# Fuel_Cell_Controller_V1.net
KiCad netlist of a schematic drawn in EAGLE
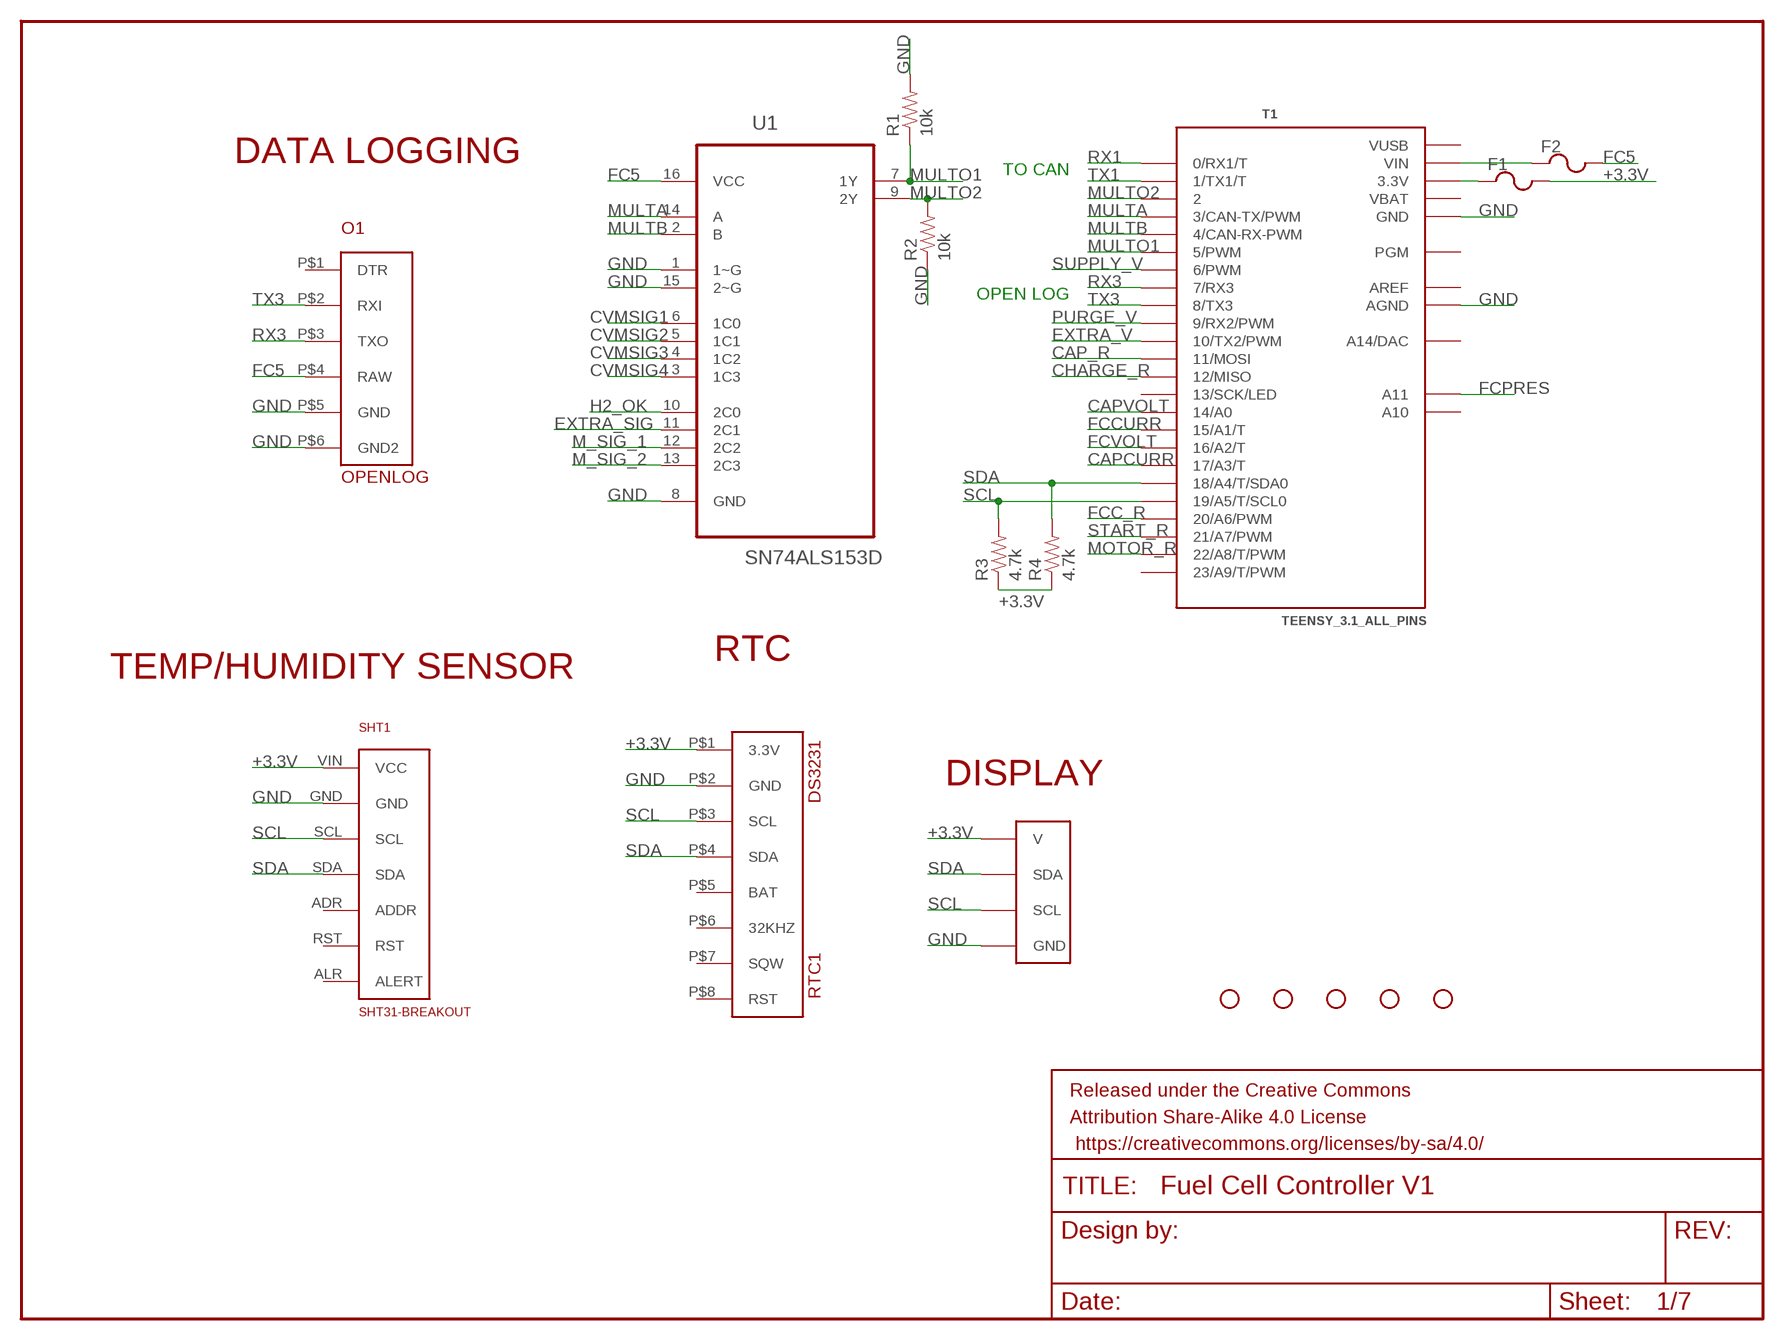
[diagram p0: schematic, sheet 1]
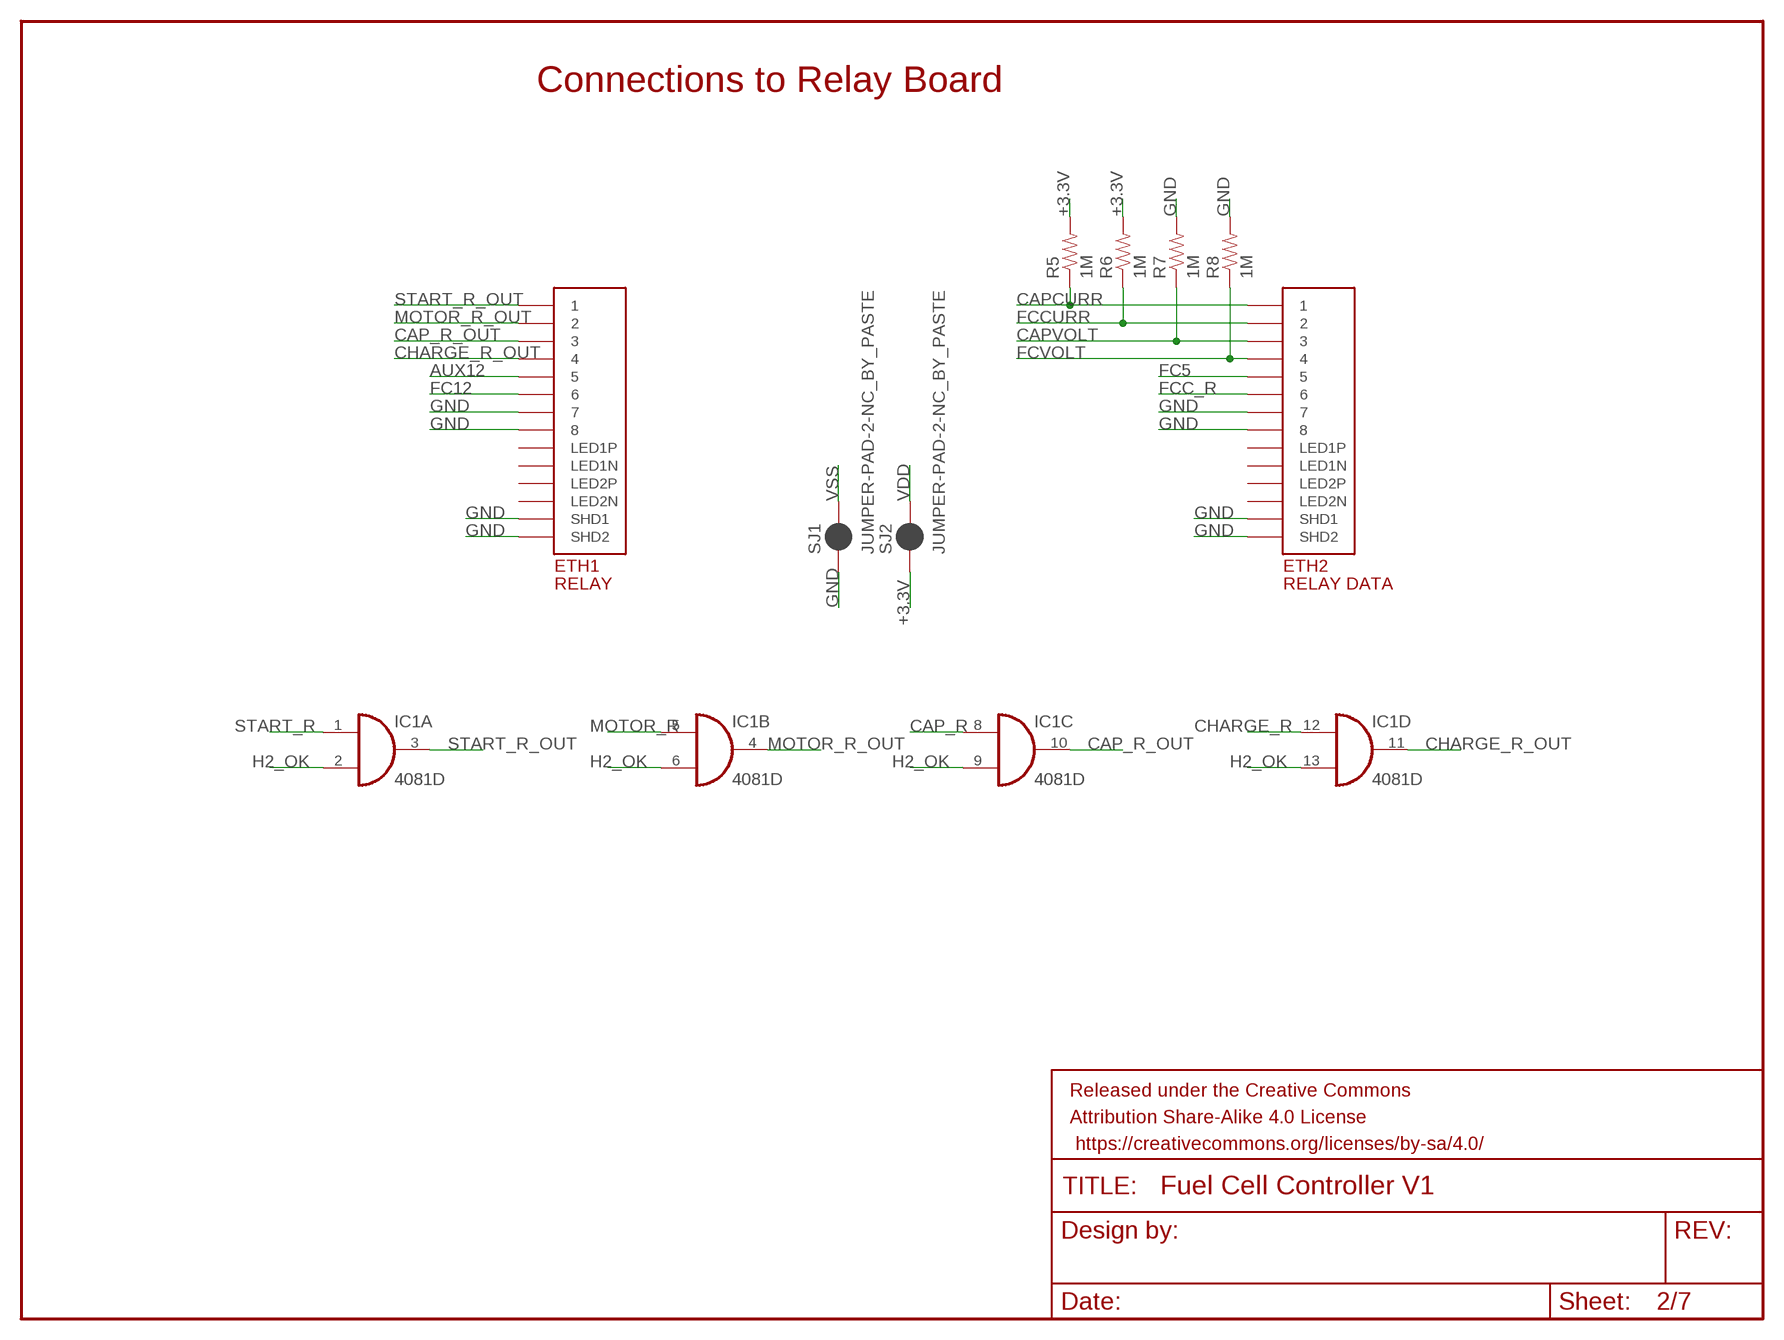
[diagram p1: schematic, sheet 2]
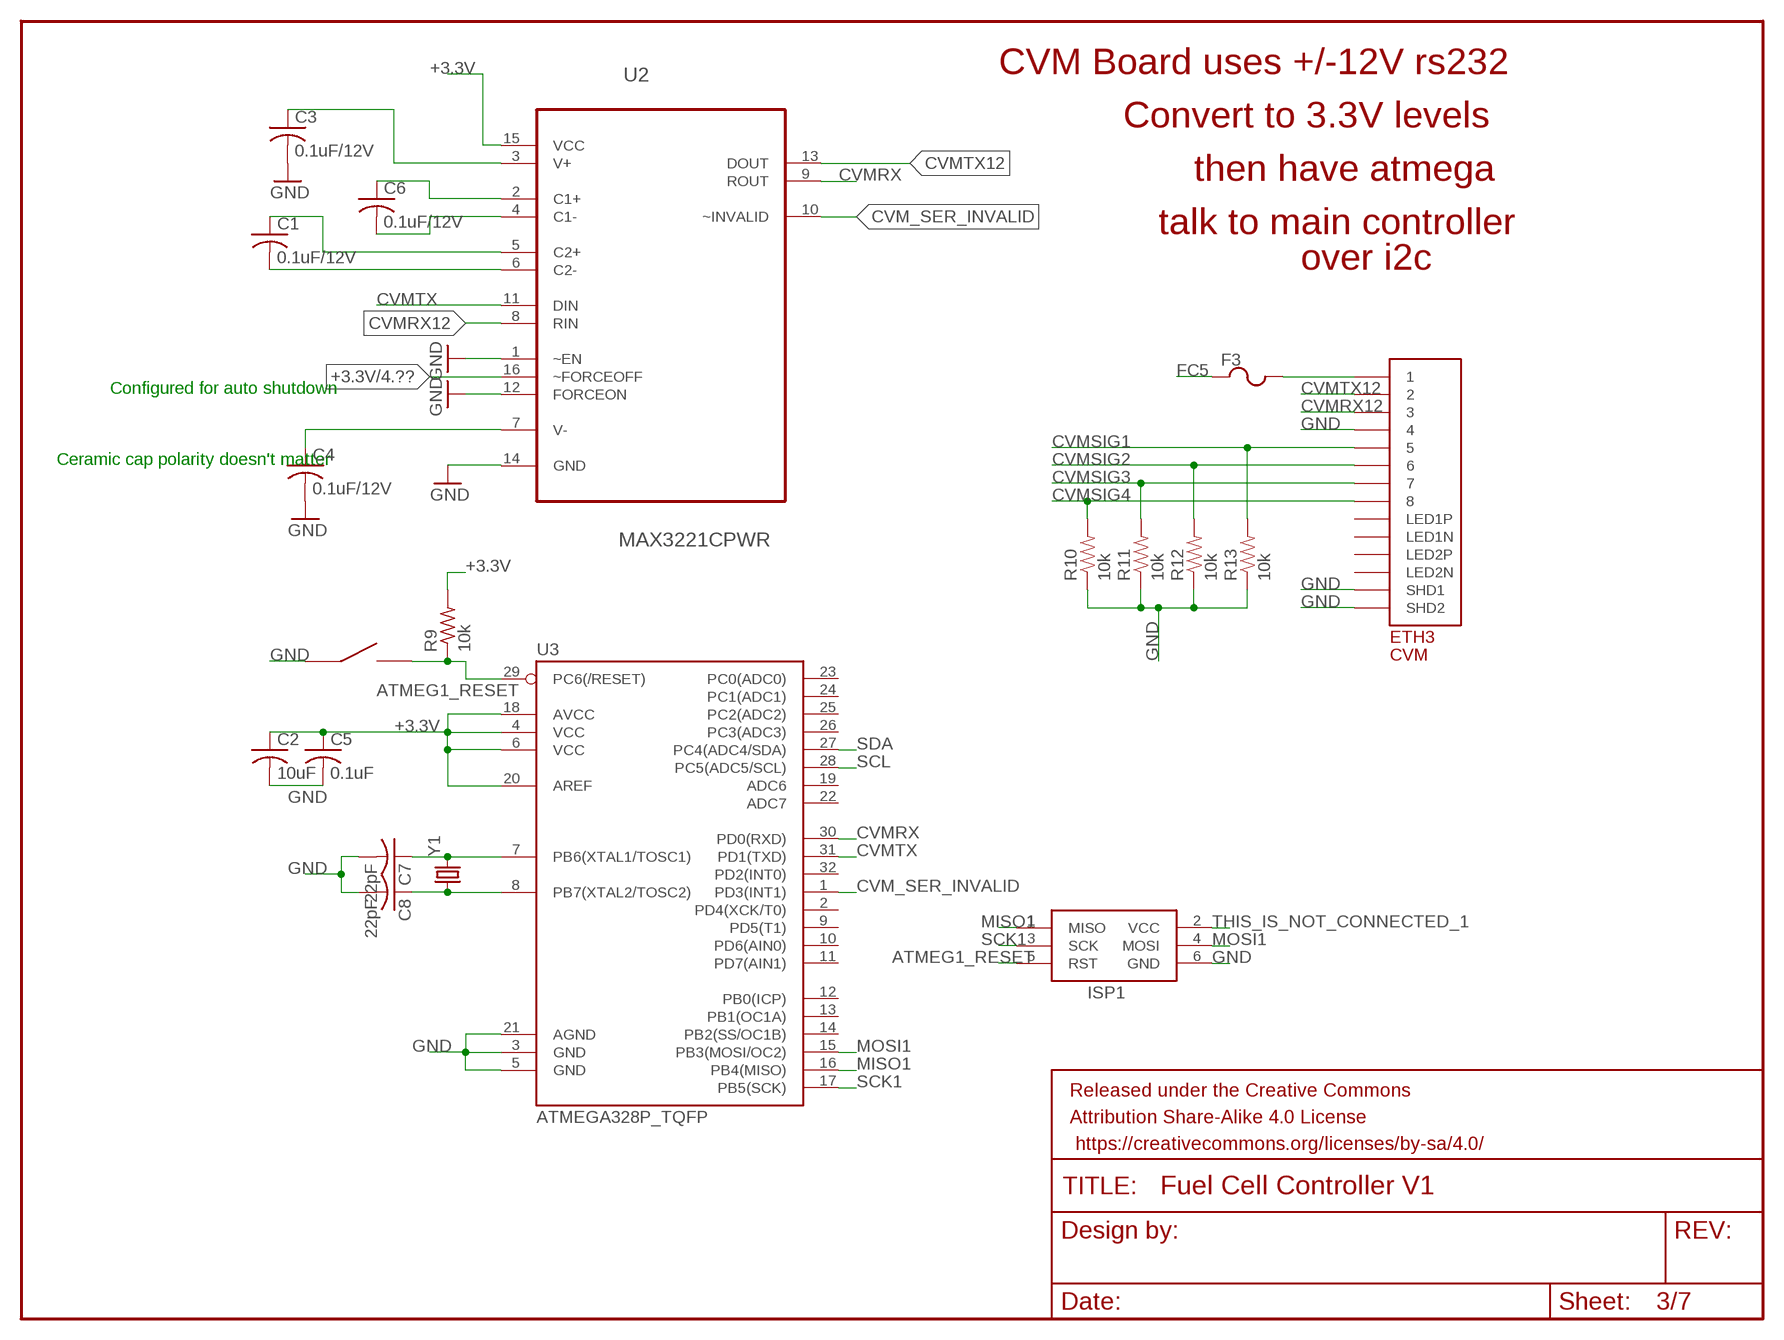
[diagram p2: schematic, sheet 3]
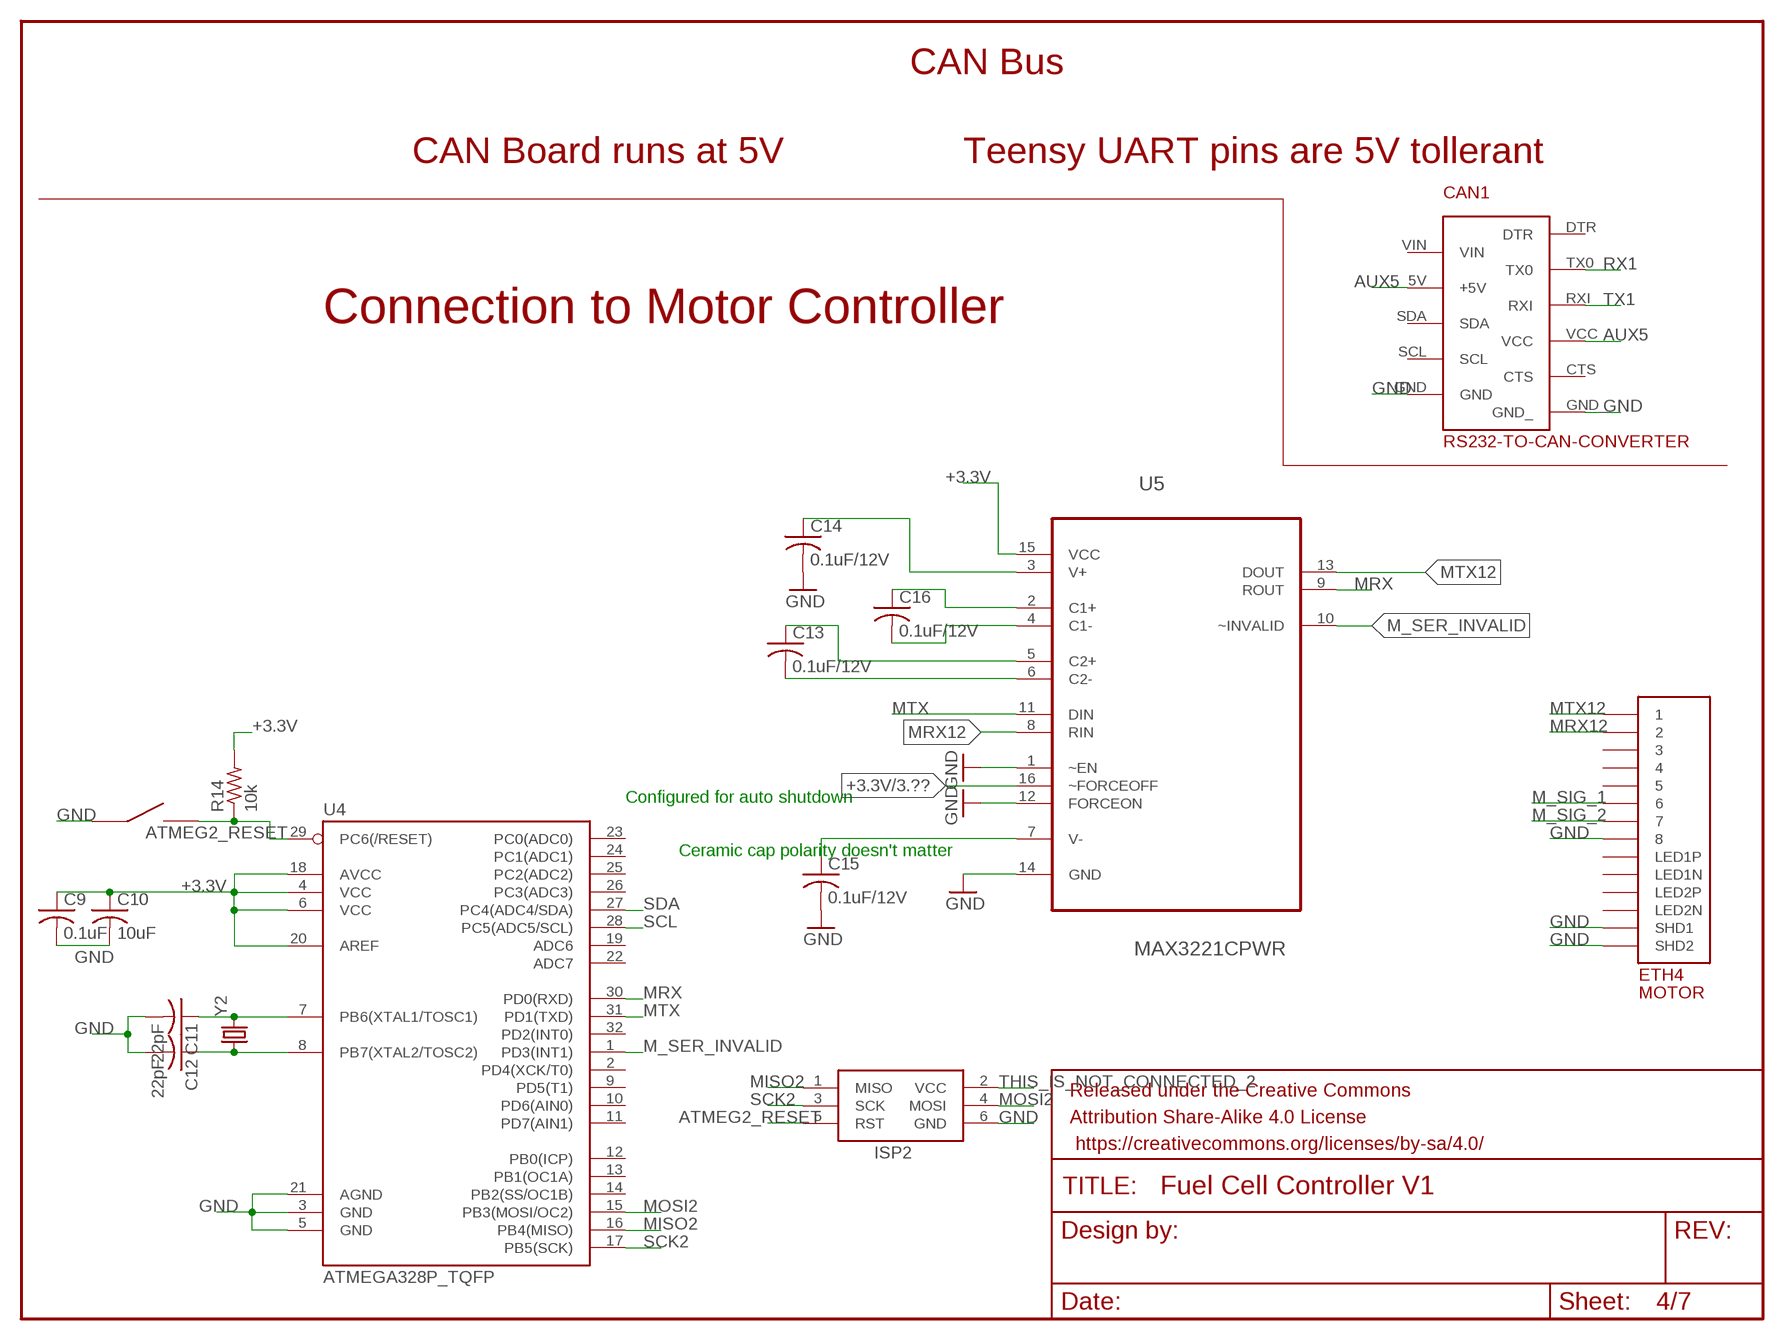
[diagram p3: schematic, sheet 4]
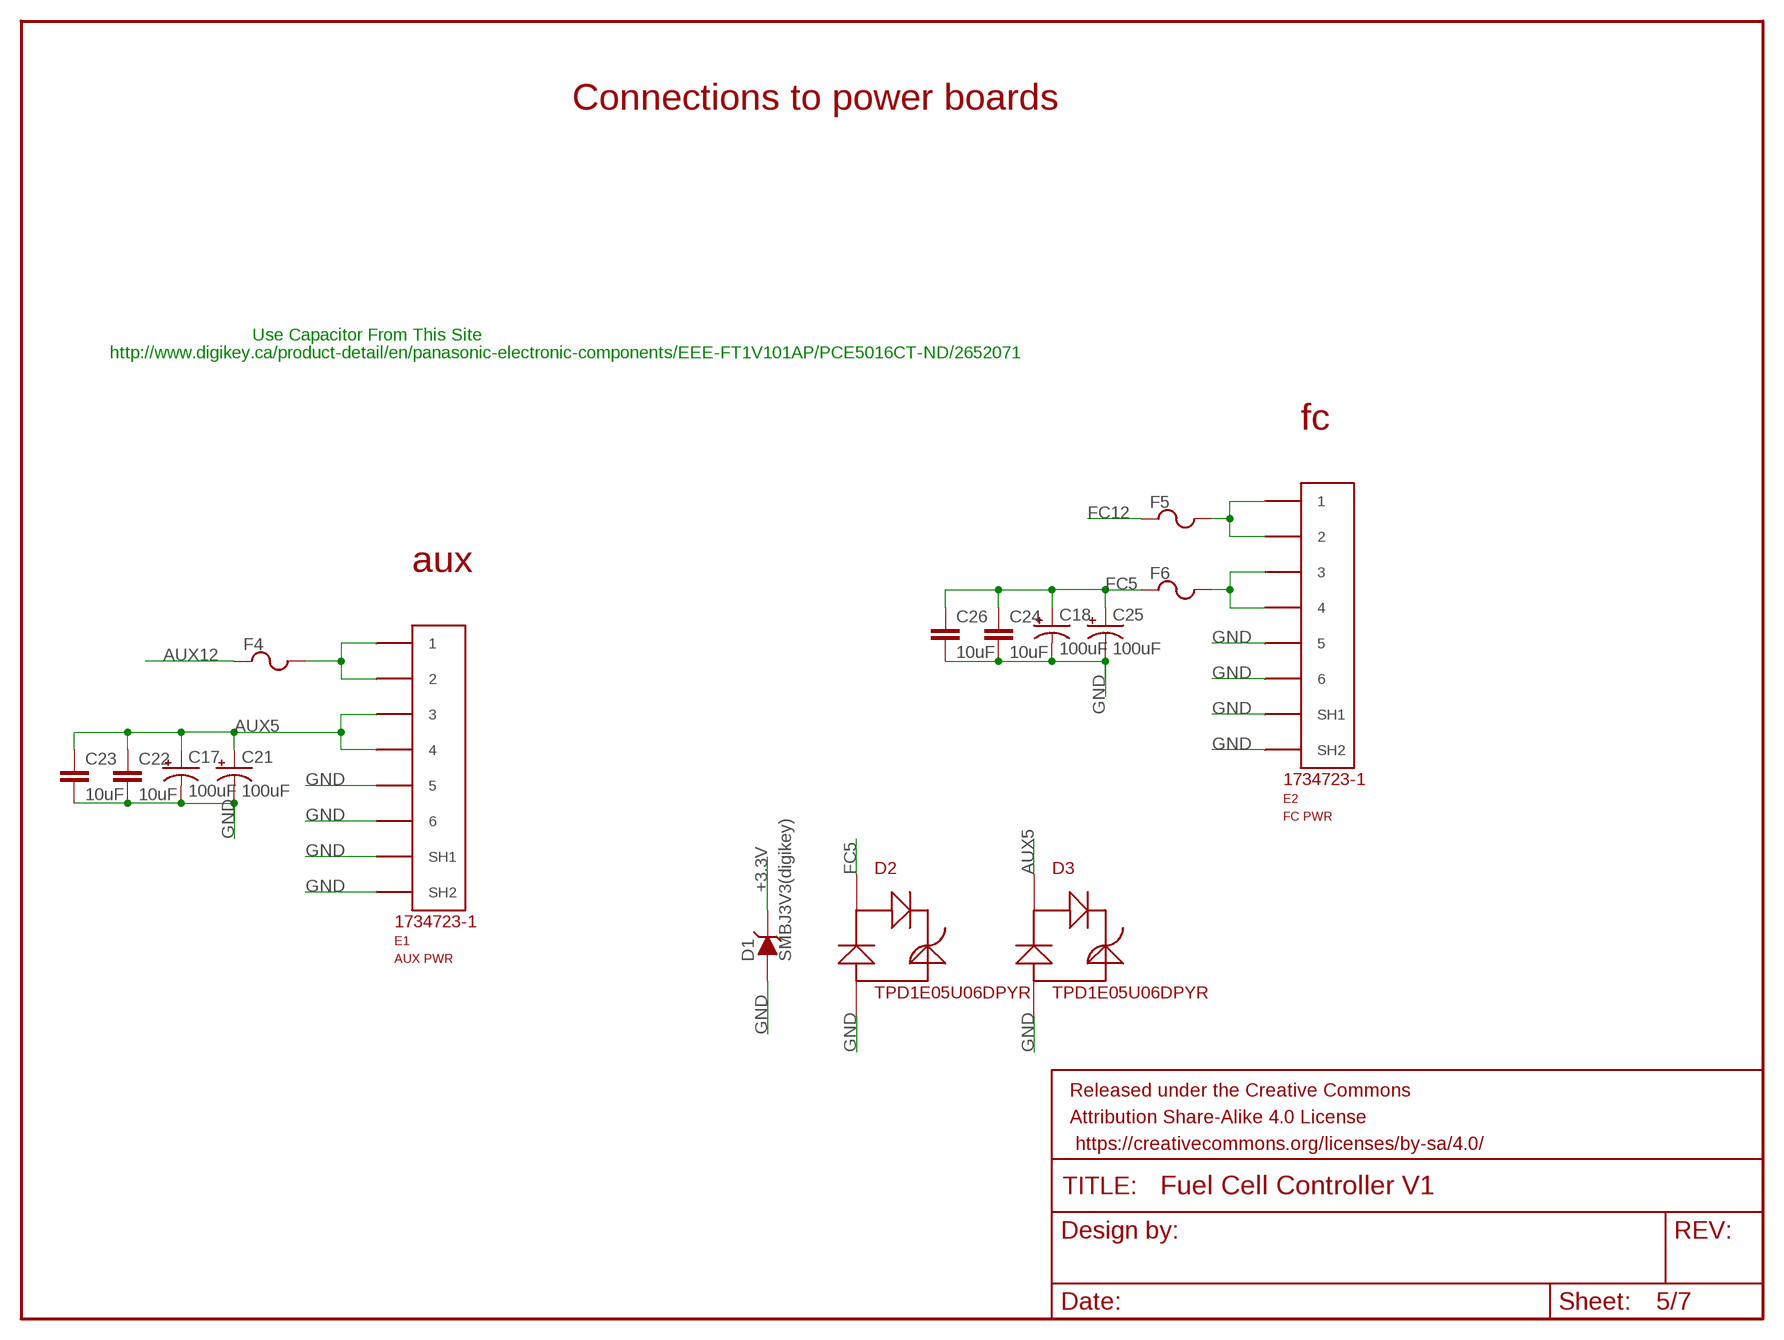
[diagram p4: schematic, sheet 5]
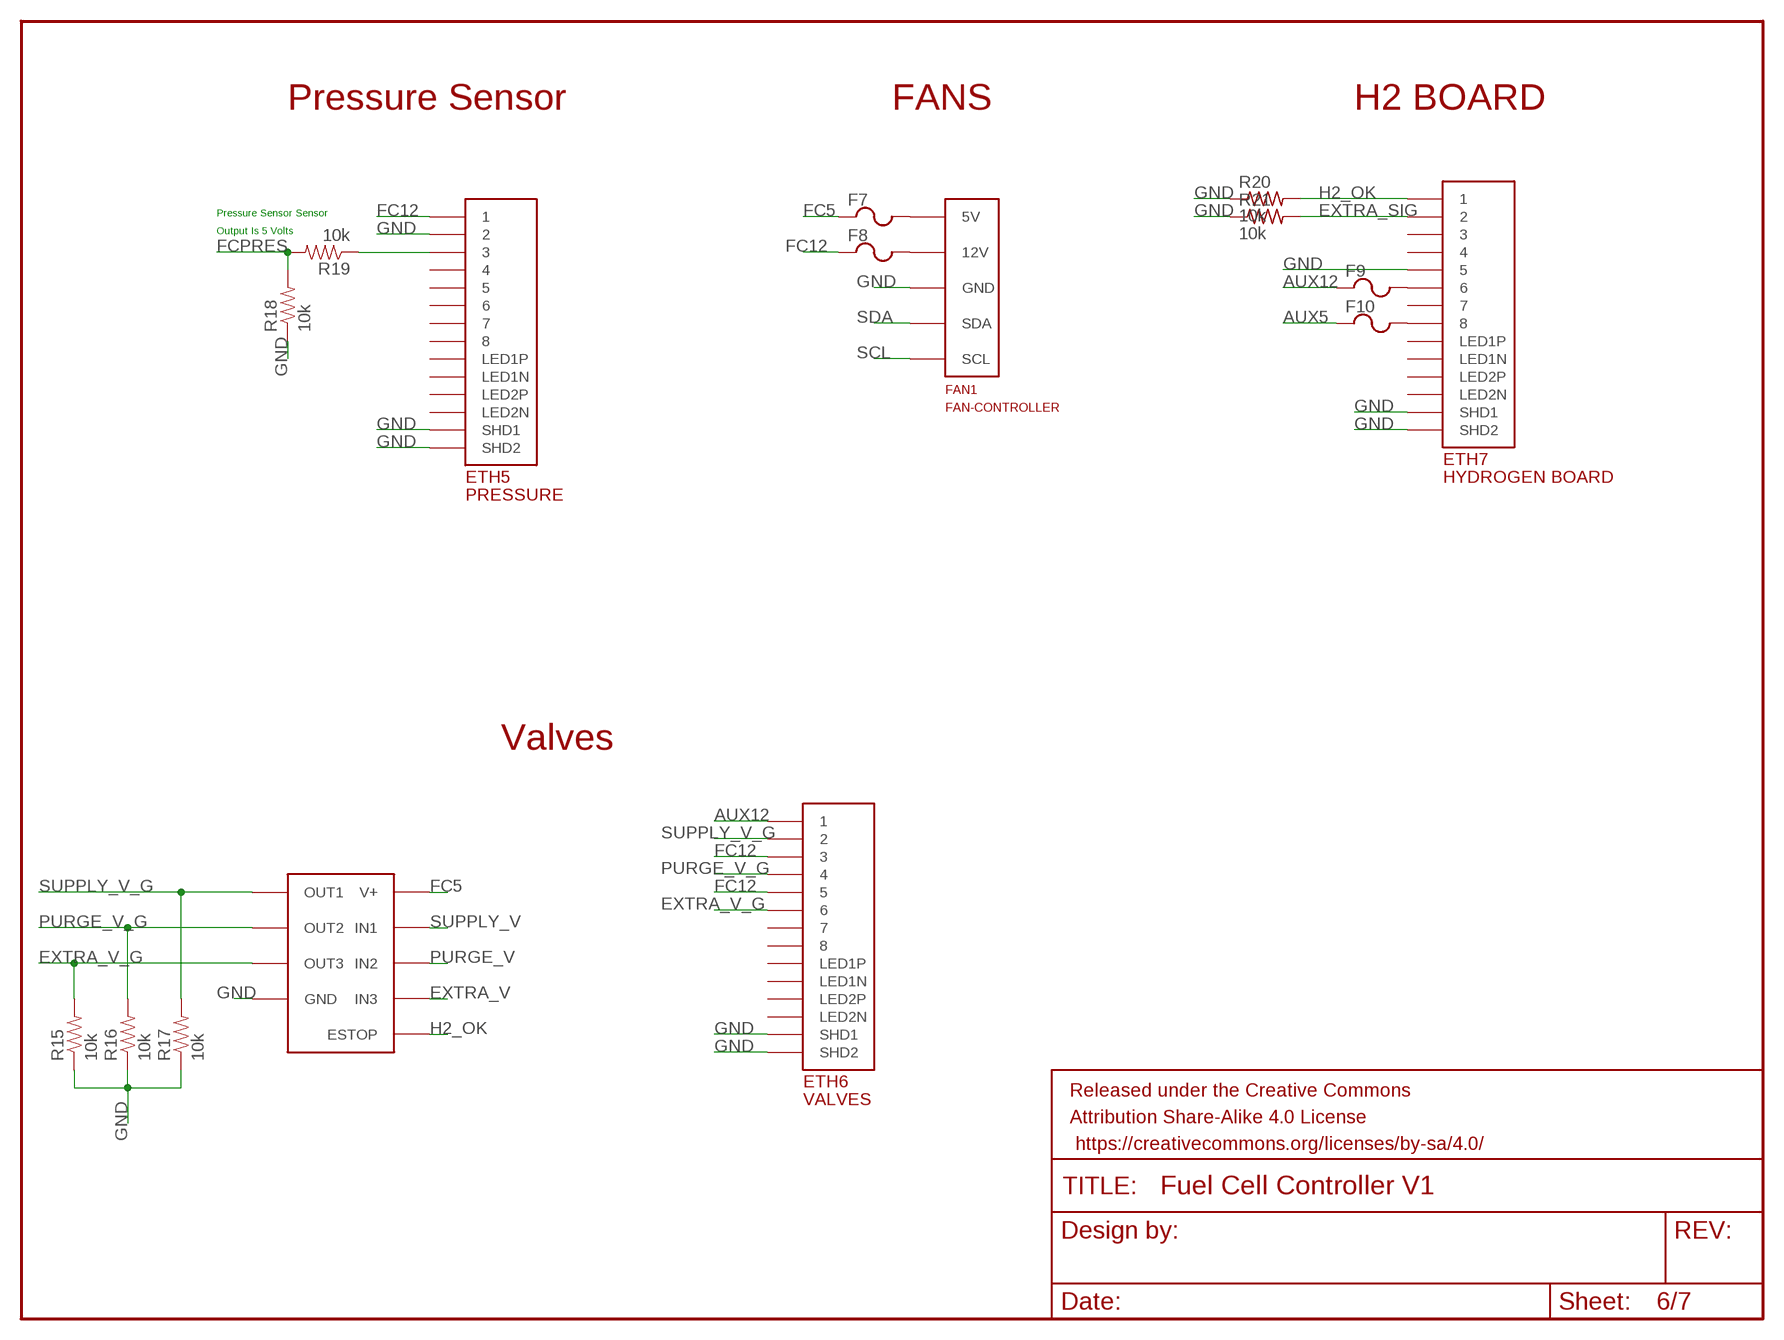
[diagram p5: schematic, sheet 6]
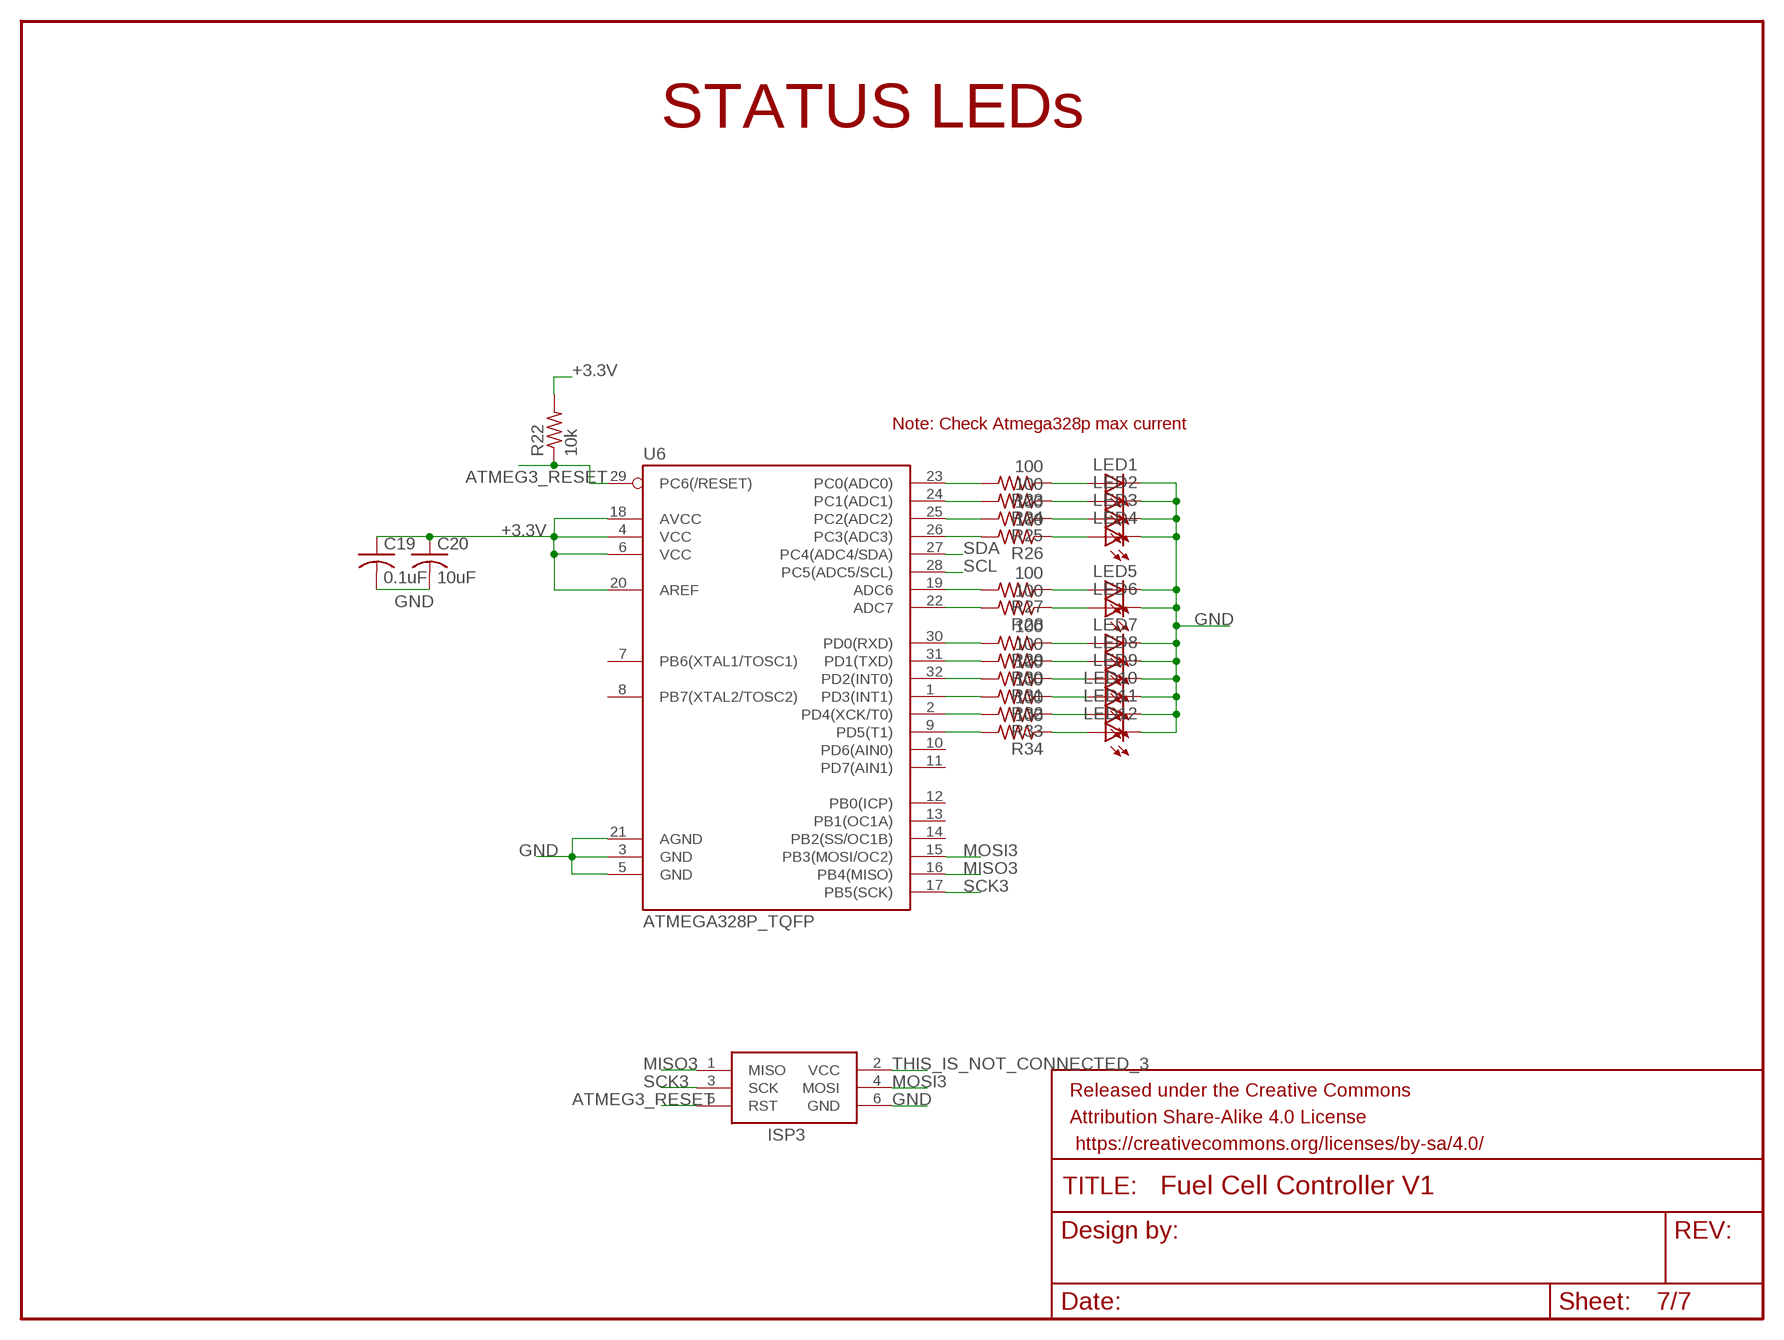
[diagram p6: schematic, sheet 7]

(export (version "E")
  (design (tool "Eeschema 10.0.6"))
  (components
    (comp (ref "F1")
      (value "POLYFUSE")
      (footprint "eagle-import:1206")
      (libsource (lib "eagle-import") (part "POLYFUSE"))
    )
    (comp (ref "F2")
      (value "POLYFUSE")
      (footprint "eagle-import:1206")
      (libsource (lib "eagle-import") (part "POLYFUSE"))
    )
    (comp (ref "FRAME1")
      (value "FRAME-LETTERNO_PACKAGE")
      (footprint "eagle-import:DUMMY")
      (fields (field (name "DESIGNER") "Reegan McAllister"))
      (libsource (lib "eagle-import") (part "FRAME-LETTERNO_PACKAGE"))
    )
    (comp (ref "LCD1")
      (value "LCD-BOARD")
      (footprint "eagle-import:LCD-BOARD")
      (libsource (lib "eagle-import") (part "LCD-BOARD"))
    )
    (comp (ref "O1")
      (value "OPENLOG")
      (footprint "eagle-import:OPENLOG")
      (libsource (lib "eagle-import") (part "OPENLOG"))
    )
    (comp (ref "R1")
      (value "10k")
      (footprint "eagle-import:0805")
      (libsource (lib "eagle-import") (part "RESISTOR0805-RES"))
    )
    (comp (ref "R2")
      (value "10k")
      (footprint "eagle-import:0805")
      (libsource (lib "eagle-import") (part "RESISTOR0805-RES"))
    )
    (comp (ref "R3")
      (value "4.7k")
      (footprint "eagle-import:0805")
      (libsource (lib "eagle-import") (part "RESISTOR0805-RES"))
    )
    (comp (ref "R4")
      (value "4.7k")
      (footprint "eagle-import:0805")
      (libsource (lib "eagle-import") (part "RESISTOR0805-RES"))
    )
    (comp (ref "RTC1")
      (value "DS3231")
      (footprint "eagle-import:DS3231")
      (libsource (lib "eagle-import") (part "DS3231"))
    )
    (comp (ref "SHT1")
      (value "SHT31-BREAKOUT")
      (footprint "eagle-import:SHT31-BREAKOUT")
      (libsource (lib "eagle-import") (part "SHT31-BREAKOUT"))
    )
    (comp (ref "STANDOFF1")
      (value "STAND-OFF")
      (footprint "eagle-import:STAND-OFF")
      (libsource (lib "eagle-import") (part "STAND-OFF"))
    )
    (comp (ref "STANDOFF2")
      (value "STAND-OFF")
      (footprint "eagle-import:STAND-OFF")
      (libsource (lib "eagle-import") (part "STAND-OFF"))
    )
    (comp (ref "STANDOFF3")
      (value "STAND-OFF")
      (footprint "eagle-import:STAND-OFF")
      (libsource (lib "eagle-import") (part "STAND-OFF"))
    )
    (comp (ref "STANDOFF4")
      (value "STAND-OFF")
      (footprint "eagle-import:STAND-OFF")
      (libsource (lib "eagle-import") (part "STAND-OFF"))
    )
    (comp (ref "STANDOFF5")
      (value "STAND-OFF")
      (footprint "eagle-import:STAND-OFF")
      (libsource (lib "eagle-import") (part "STAND-OFF"))
    )
    (comp (ref "T1")
      (value "TEENSY_3.1_ALL_PINS")
      (footprint "eagle-import:TEENSY3-ALL_PINS")
      (libsource (lib "eagle-import") (part "TEENSY_3.1_ALL_PINS"))
    )
    (comp (ref "U1")
      (value "SN74ALS153D")
      (footprint "eagle-import:SOIC127P600X175-16N")
      (libsource (lib "eagle-import") (part "SN74ALS153D"))
    )
    (comp (ref "C17")
      (value "100uF")
      (footprint "eagle-import:PANASONIC_D")
      (libsource (lib "eagle-import") (part "CAP_POLD"))
    )
    (comp (ref "C18")
      (value "100uF")
      (footprint "eagle-import:PANASONIC_D")
      (libsource (lib "eagle-import") (part "CAP_POLD"))
    )
    (comp (ref "C21")
      (value "100uF")
      (footprint "eagle-import:PANASONIC_D")
      (libsource (lib "eagle-import") (part "CAP_POLD"))
    )
    (comp (ref "C22")
      (value "10uF")
      (footprint "eagle-import:0805")
      (libsource (lib "eagle-import") (part "CAP0805"))
    )
    (comp (ref "C23")
      (value "10uF")
      (footprint "eagle-import:0805")
      (libsource (lib "eagle-import") (part "CAP0805"))
    )
    (comp (ref "C24")
      (value "10uF")
      (footprint "eagle-import:0805")
      (libsource (lib "eagle-import") (part "CAP0805"))
    )
    (comp (ref "C25")
      (value "100uF")
      (footprint "eagle-import:PANASONIC_D")
      (libsource (lib "eagle-import") (part "CAP_POLD"))
    )
    (comp (ref "C26")
      (value "10uF")
      (footprint "eagle-import:0805")
      (libsource (lib "eagle-import") (part "CAP0805"))
    )
    (comp (ref "D1")
      (value "SMBJ3V3(digikey)")
      (footprint "eagle-import:DO-214AB")
      (libsource (lib "eagle-import") (part "5KASMC"))
    )
    (comp (ref "D2")
      (value "TPD1E05U06DPYR")
      (footprint "eagle-import:2-XDFN")
      (libsource (lib "eagle-import") (part "TPD1E05U06DPYR"))
    )
    (comp (ref "D3")
      (value "TPD1E05U06DPYR")
      (footprint "eagle-import:2-XDFN")
      (libsource (lib "eagle-import") (part "TPD1E05U06DPYR"))
    )
    (comp (ref "E1")
      (value "AUX PWR")
      (footprint "eagle-import:1734723-1_RJ11")
      (libsource (lib "eagle-import") (part "5555140-6"))
    )
    (comp (ref "E2")
      (value "FC PWR")
      (footprint "eagle-import:1734723-1_RJ11")
      (libsource (lib "eagle-import") (part "5555140-6"))
    )
    (comp (ref "F4")
      (value "POLYFUSE")
      (footprint "eagle-import:1206")
      (libsource (lib "eagle-import") (part "POLYFUSE"))
    )
    (comp (ref "F5")
      (value "POLYFUSE")
      (footprint "eagle-import:1206")
      (libsource (lib "eagle-import") (part "POLYFUSE"))
    )
    (comp (ref "F6")
      (value "POLYFUSE")
      (footprint "eagle-import:1206")
      (libsource (lib "eagle-import") (part "POLYFUSE"))
    )
    (comp (ref "FRAME5")
      (value "FRAME-LETTERNO_PACKAGE")
      (footprint "eagle-import:DUMMY")
      (fields (field (name "DESIGNER") "Nobody"))
      (libsource (lib "eagle-import") (part "FRAME-LETTERNO_PACKAGE"))
    )
    (comp (ref "C19")
      (value "0.1uF")
      (footprint "eagle-import:C0603")
      (libsource (lib "eagle-import") (part "adafruit_C-USC0603"))
    )
    (comp (ref "C20")
      (value "10uF")
      (footprint "eagle-import:C0603")
      (libsource (lib "eagle-import") (part "adafruit_C-USC0603"))
    )
    (comp (ref "FRAME7")
      (value "FRAME-LETTERNO_PACKAGE")
      (footprint "eagle-import:DUMMY")
      (fields (field (name "DESIGNER") "Nobody"))
      (libsource (lib "eagle-import") (part "FRAME-LETTERNO_PACKAGE"))
    )
    (comp (ref "ISP3")
      (value "AVRISP-BOX")
      (footprint "eagle-import:AVRISP-BOX")
      (libsource (lib "eagle-import") (part "AVRISP-BOX"))
    )
    (comp (ref "LED1")
      (value "LEDCHIPLED_0805")
      (footprint "eagle-import:CHIPLED_0805")
      (libsource (lib "eagle-import") (part "LEDCHIPLED_0805"))
    )
    (comp (ref "LED2")
      (value "LEDCHIPLED_0805")
      (footprint "eagle-import:CHIPLED_0805")
      (libsource (lib "eagle-import") (part "LEDCHIPLED_0805"))
    )
    (comp (ref "LED3")
      (value "LEDCHIPLED_0805")
      (footprint "eagle-import:CHIPLED_0805")
      (libsource (lib "eagle-import") (part "LEDCHIPLED_0805"))
    )
    (comp (ref "LED4")
      (value "LEDCHIPLED_0805")
      (footprint "eagle-import:CHIPLED_0805")
      (libsource (lib "eagle-import") (part "LEDCHIPLED_0805"))
    )
    (comp (ref "LED5")
      (value "LEDCHIPLED_0805")
      (footprint "eagle-import:CHIPLED_0805")
      (libsource (lib "eagle-import") (part "LEDCHIPLED_0805"))
    )
    (comp (ref "LED6")
      (value "LEDCHIPLED_0805")
      (footprint "eagle-import:CHIPLED_0805")
      (libsource (lib "eagle-import") (part "LEDCHIPLED_0805"))
    )
    (comp (ref "LED7")
      (value "LEDCHIPLED_0805")
      (footprint "eagle-import:CHIPLED_0805")
      (libsource (lib "eagle-import") (part "LEDCHIPLED_0805"))
    )
    (comp (ref "LED8")
      (value "LEDCHIPLED_0805")
      (footprint "eagle-import:CHIPLED_0805")
      (libsource (lib "eagle-import") (part "LEDCHIPLED_0805"))
    )
    (comp (ref "LED9")
      (value "LEDCHIPLED_0805")
      (footprint "eagle-import:CHIPLED_0805")
      (libsource (lib "eagle-import") (part "LEDCHIPLED_0805"))
    )
    (comp (ref "LED10")
      (value "LEDCHIPLED_0805")
      (footprint "eagle-import:CHIPLED_0805")
      (libsource (lib "eagle-import") (part "LEDCHIPLED_0805"))
    )
    (comp (ref "LED11")
      (value "LEDCHIPLED_0805")
      (footprint "eagle-import:CHIPLED_0805")
      (libsource (lib "eagle-import") (part "LEDCHIPLED_0805"))
    )
    (comp (ref "LED12")
      (value "LEDCHIPLED_0805")
      (footprint "eagle-import:CHIPLED_0805")
      (libsource (lib "eagle-import") (part "LEDCHIPLED_0805"))
    )
    (comp (ref "R22")
      (value "10k")
      (footprint "eagle-import:R0603")
      (libsource (lib "eagle-import") (part "R-US_R0603"))
    )
    (comp (ref "R23")
      (value "100")
      (footprint "eagle-import:R0603")
      (libsource (lib "eagle-import") (part "R-US_R0603"))
    )
    (comp (ref "R24")
      (value "100")
      (footprint "eagle-import:R0603")
      (libsource (lib "eagle-import") (part "R-US_R0603"))
    )
    (comp (ref "R25")
      (value "100")
      (footprint "eagle-import:R0603")
      (libsource (lib "eagle-import") (part "R-US_R0603"))
    )
    (comp (ref "R26")
      (value "100")
      (footprint "eagle-import:R0603")
      (libsource (lib "eagle-import") (part "R-US_R0603"))
    )
    (comp (ref "R27")
      (value "100")
      (footprint "eagle-import:R0603")
      (libsource (lib "eagle-import") (part "R-US_R0603"))
    )
    (comp (ref "R28")
      (value "100")
      (footprint "eagle-import:R0603")
      (libsource (lib "eagle-import") (part "R-US_R0603"))
    )
    (comp (ref "R29")
      (value "100")
      (footprint "eagle-import:R0603")
      (libsource (lib "eagle-import") (part "R-US_R0603"))
    )
    (comp (ref "R30")
      (value "100")
      (footprint "eagle-import:R0603")
      (libsource (lib "eagle-import") (part "R-US_R0603"))
    )
    (comp (ref "R31")
      (value "100")
      (footprint "eagle-import:R0603")
      (libsource (lib "eagle-import") (part "R-US_R0603"))
    )
    (comp (ref "R32")
      (value "100")
      (footprint "eagle-import:R0603")
      (libsource (lib "eagle-import") (part "R-US_R0603"))
    )
    (comp (ref "R33")
      (value "100")
      (footprint "eagle-import:R0603")
      (libsource (lib "eagle-import") (part "R-US_R0603"))
    )
    (comp (ref "R34")
      (value "100")
      (footprint "eagle-import:R0603")
      (libsource (lib "eagle-import") (part "R-US_R0603"))
    )
    (comp (ref "U6")
      (value "ATMEGA328P_TQFP")
      (footprint "eagle-import:TQFP32-08")
      (libsource (lib "eagle-import") (part "ATMEGA328P_TQFP"))
    )
    (comp (ref "C9")
      (value "0.1uF")
      (footprint "eagle-import:C0603")
      (libsource (lib "eagle-import") (part "adafruit_C-USC0603"))
    )
    (comp (ref "C10")
      (value "10uF")
      (footprint "eagle-import:C0603")
      (libsource (lib "eagle-import") (part "adafruit_C-USC0603"))
    )
    (comp (ref "C11")
      (value "22pF")
      (footprint "eagle-import:C0603")
      (libsource (lib "eagle-import") (part "adafruit_C-USC0603"))
    )
    (comp (ref "C12")
      (value "22pF")
      (footprint "eagle-import:C0603")
      (libsource (lib "eagle-import") (part "adafruit_C-USC0603"))
    )
    (comp (ref "C13")
      (value "0.1uF/12V")
      (footprint "eagle-import:C0805")
      (libsource (lib "eagle-import") (part "C-USC0805"))
    )
    (comp (ref "C14")
      (value "0.1uF/12V")
      (footprint "eagle-import:C0805")
      (libsource (lib "eagle-import") (part "C-USC0805"))
    )
    (comp (ref "C15")
      (value "0.1uF/12V")
      (footprint "eagle-import:C0805")
      (libsource (lib "eagle-import") (part "C-USC0805"))
    )
    (comp (ref "C16")
      (value "0.1uF/12V")
      (footprint "eagle-import:C0805")
      (libsource (lib "eagle-import") (part "C-USC0805"))
    )
    (comp (ref "CAN1")
      (value "RS232-TO-CAN-CONVERTER")
      (footprint "eagle-import:RS232-TO-CAN-CONVERTER")
      (libsource (lib "eagle-import") (part "RS232-TO-CAN-CONVERTER"))
    )
    (comp (ref "ETH4")
      (value "MOTOR")
      (footprint "eagle-import:A122645-ND")
      (libsource (lib "eagle-import") (part "ETHERNET"))
    )
    (comp (ref "FRAME4")
      (value "FRAME-LETTERNO_PACKAGE")
      (footprint "eagle-import:DUMMY")
      (fields (field (name "DESIGNER") "Nobody"))
      (libsource (lib "eagle-import") (part "FRAME-LETTERNO_PACKAGE"))
    )
    (comp (ref "ISP2")
      (value "AVRISP-BOX")
      (footprint "eagle-import:AVRISP-BOX")
      (libsource (lib "eagle-import") (part "AVRISP-BOX"))
    )
    (comp (ref "R14")
      (value "10k")
      (footprint "eagle-import:R0603")
      (libsource (lib "eagle-import") (part "R-US_R0603"))
    )
    (comp (ref "S2")
      (value "EG4621CT-ND")
      (footprint "eagle-import:EG4621CT-ND")
      (libsource (lib "eagle-import") (part "EG4621CT-ND"))
    )
    (comp (ref "U4")
      (value "ATMEGA328P_TQFP")
      (footprint "eagle-import:TQFP32-08")
      (libsource (lib "eagle-import") (part "ATMEGA328P_TQFP"))
    )
    (comp (ref "U5")
      (value "MAX3221CPWR")
      (footprint "eagle-import:SOP65P640X120-16N")
      (libsource (lib "eagle-import") (part "MAX3221CPWR"))
    )
    (comp (ref "Y2")
      (value "CRYSTALHC49US")
      (footprint "eagle-import:HC49US")
      (libsource (lib "eagle-import") (part "CRYSTALHC49US"))
    )
    (comp (ref "ETH1")
      (value "RELAY")
      (footprint "eagle-import:A122645-ND")
      (libsource (lib "eagle-import") (part "ETHERNET"))
    )
    (comp (ref "ETH2")
      (value "RELAY DATA")
      (footprint "eagle-import:A122645-ND")
      (libsource (lib "eagle-import") (part "ETHERNET"))
    )
    (comp (ref "FRAME2")
      (value "FRAME-LETTERNO_PACKAGE")
      (footprint "eagle-import:DUMMY")
      (fields (field (name "DESIGNER") "Nobody"))
      (libsource (lib "eagle-import") (part "FRAME-LETTERNO_PACKAGE"))
    )
    (comp (ref "IC1")
      (value "4081D")
      (footprint "eagle-import:SO14")
      (libsource (lib "eagle-import") (part "4081D"))
    )
    (comp (ref "R5")
      (value "1M")
      (footprint "eagle-import:0805")
      (libsource (lib "eagle-import") (part "RESISTOR0805-RES"))
    )
    (comp (ref "R6")
      (value "1M")
      (footprint "eagle-import:0805")
      (libsource (lib "eagle-import") (part "RESISTOR0805-RES"))
    )
    (comp (ref "R7")
      (value "1M")
      (footprint "eagle-import:0805")
      (libsource (lib "eagle-import") (part "RESISTOR0805-RES"))
    )
    (comp (ref "R8")
      (value "1M")
      (footprint "eagle-import:0805")
      (libsource (lib "eagle-import") (part "RESISTOR0805-RES"))
    )
    (comp (ref "SJ1")
      (value "JUMPER-PAD-2-NC_BY_PASTE")
      (footprint "eagle-import:PAD-JUMPER-2-NC_BY_PASTE_YES_SILK")
      (libsource (lib "eagle-import") (part "JUMPER-PAD-2-NC_BY_PASTE"))
    )
    (comp (ref "SJ2")
      (value "JUMPER-PAD-2-NC_BY_PASTE")
      (footprint "eagle-import:PAD-JUMPER-2-NC_BY_PASTE_YES_SILK")
      (libsource (lib "eagle-import") (part "JUMPER-PAD-2-NC_BY_PASTE"))
    )
    (comp (ref "ETH5")
      (value "PRESSURE")
      (footprint "eagle-import:A122645-ND")
      (libsource (lib "eagle-import") (part "ETHERNET"))
    )
    (comp (ref "ETH6")
      (value "VALVES")
      (footprint "eagle-import:A122645-ND")
      (libsource (lib "eagle-import") (part "ETHERNET"))
    )
    (comp (ref "ETH7")
      (value "HYDROGEN BOARD")
      (footprint "eagle-import:A122645-ND")
      (libsource (lib "eagle-import") (part "ETHERNET"))
    )
    (comp (ref "F7")
      (value "POLYFUSE")
      (footprint "eagle-import:1206")
      (libsource (lib "eagle-import") (part "POLYFUSE"))
    )
    (comp (ref "F8")
      (value "POLYFUSE")
      (footprint "eagle-import:1206")
      (libsource (lib "eagle-import") (part "POLYFUSE"))
    )
    (comp (ref "F9")
      (value "POLYFUSE")
      (footprint "eagle-import:1206")
      (libsource (lib "eagle-import") (part "POLYFUSE"))
    )
    (comp (ref "F10")
      (value "POLYFUSE")
      (footprint "eagle-import:1206")
      (libsource (lib "eagle-import") (part "POLYFUSE"))
    )
    (comp (ref "FAN1")
      (value "FAN-CONTROLLER")
      (footprint "eagle-import:FAN-CONTROLLER")
      (libsource (lib "eagle-import") (part "FAN-CONTROLLER"))
    )
    (comp (ref "FRAME6")
      (value "FRAME-LETTERNO_PACKAGE")
      (footprint "eagle-import:DUMMY")
      (fields (field (name "DESIGNER") "Nobody"))
      (libsource (lib "eagle-import") (part "FRAME-LETTERNO_PACKAGE"))
    )
    (comp (ref "M1")
      (value "MOSFETBOARD")
      (footprint "eagle-import:MOSFET-BOARD")
      (libsource (lib "eagle-import") (part "MOSFETBOARD"))
    )
    (comp (ref "R15")
      (value "10k")
      (footprint "eagle-import:0805")
      (libsource (lib "eagle-import") (part "RESISTOR0805-RES"))
    )
    (comp (ref "R16")
      (value "10k")
      (footprint "eagle-import:0805")
      (libsource (lib "eagle-import") (part "RESISTOR0805-RES"))
    )
    (comp (ref "R17")
      (value "10k")
      (footprint "eagle-import:0805")
      (libsource (lib "eagle-import") (part "RESISTOR0805-RES"))
    )
    (comp (ref "R18")
      (value "10k")
      (footprint "eagle-import:0805")
      (libsource (lib "eagle-import") (part "RESISTOR0805-RES"))
    )
    (comp (ref "R19")
      (value "10k")
      (footprint "eagle-import:0805")
      (libsource (lib "eagle-import") (part "RESISTOR0805-RES"))
    )
    (comp (ref "R20")
      (value "10k")
      (footprint "eagle-import:R0603")
      (libsource (lib "eagle-import") (part "R-US_R0603"))
    )
    (comp (ref "R21")
      (value "10k")
      (footprint "eagle-import:R0603")
      (libsource (lib "eagle-import") (part "R-US_R0603"))
    )
    (comp (ref "C1")
      (value "0.1uF/12V")
      (footprint "eagle-import:C0805")
      (libsource (lib "eagle-import") (part "C-USC0805"))
    )
    (comp (ref "C2")
      (value "10uF")
      (footprint "eagle-import:C0603")
      (libsource (lib "eagle-import") (part "adafruit_C-USC0603"))
    )
    (comp (ref "C3")
      (value "0.1uF/12V")
      (footprint "eagle-import:C0805")
      (libsource (lib "eagle-import") (part "C-USC0805"))
    )
    (comp (ref "C4")
      (value "0.1uF/12V")
      (footprint "eagle-import:C0805")
      (libsource (lib "eagle-import") (part "C-USC0805"))
    )
    (comp (ref "C5")
      (value "0.1uF")
      (footprint "eagle-import:C0603")
      (libsource (lib "eagle-import") (part "adafruit_C-USC0603"))
    )
    (comp (ref "C6")
      (value "0.1uF/12V")
      (footprint "eagle-import:C0805")
      (libsource (lib "eagle-import") (part "C-USC0805"))
    )
    (comp (ref "C7")
      (value "22pF")
      (footprint "eagle-import:C0603")
      (libsource (lib "eagle-import") (part "adafruit_C-USC0603"))
    )
    (comp (ref "C8")
      (value "22pF")
      (footprint "eagle-import:C0603")
      (libsource (lib "eagle-import") (part "adafruit_C-USC0603"))
    )
    (comp (ref "ETH3")
      (value "CVM")
      (footprint "eagle-import:A122645-ND")
      (libsource (lib "eagle-import") (part "ETHERNET"))
    )
    (comp (ref "F3")
      (value "POLYFUSE")
      (footprint "eagle-import:1206")
      (libsource (lib "eagle-import") (part "POLYFUSE"))
    )
    (comp (ref "FRAME3")
      (value "FRAME-LETTERNO_PACKAGE")
      (footprint "eagle-import:DUMMY")
      (fields (field (name "DESIGNER") "Nobody"))
      (libsource (lib "eagle-import") (part "FRAME-LETTERNO_PACKAGE"))
    )
    (comp (ref "ISP1")
      (value "AVRISP-BOX")
      (footprint "eagle-import:AVRISP-BOX")
      (libsource (lib "eagle-import") (part "AVRISP-BOX"))
    )
    (comp (ref "R9")
      (value "10k")
      (footprint "eagle-import:R0603")
      (libsource (lib "eagle-import") (part "R-US_R0603"))
    )
    (comp (ref "R10")
      (value "10k")
      (footprint "eagle-import:0805")
      (libsource (lib "eagle-import") (part "RESISTOR0805-RES"))
    )
    (comp (ref "R11")
      (value "10k")
      (footprint "eagle-import:0805")
      (libsource (lib "eagle-import") (part "RESISTOR0805-RES"))
    )
    (comp (ref "R12")
      (value "10k")
      (footprint "eagle-import:0805")
      (libsource (lib "eagle-import") (part "RESISTOR0805-RES"))
    )
    (comp (ref "R13")
      (value "10k")
      (footprint "eagle-import:0805")
      (libsource (lib "eagle-import") (part "RESISTOR0805-RES"))
    )
    (comp (ref "S1")
      (value "EG4621CT-ND")
      (footprint "eagle-import:EG4621CT-ND")
      (libsource (lib "eagle-import") (part "EG4621CT-ND"))
    )
    (comp (ref "U2")
      (value "MAX3221CPWR")
      (footprint "eagle-import:SOP65P640X120-16N")
      (libsource (lib "eagle-import") (part "MAX3221CPWR"))
    )
    (comp (ref "U3")
      (value "ATMEGA328P_TQFP")
      (footprint "eagle-import:TQFP32-08")
      (libsource (lib "eagle-import") (part "ATMEGA328P_TQFP"))
    )
    (comp (ref "Y1")
      (value "CRYSTALHC49US")
      (footprint "eagle-import:HC49US")
      (libsource (lib "eagle-import") (part "CRYSTALHC49US"))
    )
  )
  (nets
    (net (code "1") (name "+3.3V") (class "Default")
      (node (ref "C10") (pin "1") (pinfunction "1_1") (pintype "passive"))
      (node (ref "C19") (pin "1") (pinfunction "1_1") (pintype "passive"))
      (node (ref "C2") (pin "1") (pinfunction "1_1") (pintype "passive"))
      (node (ref "C20") (pin "1") (pinfunction "1_1") (pintype "passive"))
      (node (ref "C5") (pin "1") (pinfunction "1_1") (pintype "passive"))
      (node (ref "C9") (pin "1") (pinfunction "1_1") (pintype "passive"))
      (node (ref "D1") (pin "C") (pinfunction "C_C") (pintype "passive"))
      (node (ref "F1") (pin "2") (pinfunction "2_2") (pintype "passive"))
      (node (ref "LCD1") (pin "V") (pinfunction "V_V") (pintype "bidirectional"))
      (node (ref "R14") (pin "2") (pinfunction "2_2") (pintype "passive"))
      (node (ref "R22") (pin "2") (pinfunction "2_2") (pintype "passive"))
      (node (ref "R3") (pin "1") (pinfunction "1_1") (pintype "passive"))
      (node (ref "R4") (pin "1") (pinfunction "1_1") (pintype "passive"))
      (node (ref "R5") (pin "2") (pinfunction "2_2") (pintype "passive"))
      (node (ref "R6") (pin "2") (pinfunction "2_2") (pintype "passive"))
      (node (ref "R9") (pin "2") (pinfunction "2_2") (pintype "passive"))
      (node (ref "RTC1") (pin "P$1") (pinfunction "3.3V_P$1") (pintype "bidirectional"))
      (node (ref "SHT1") (pin "VIN") (pinfunction "VCC_VIN") (pintype "bidirectional"))
      (node (ref "SJ2") (pin "1") (pinfunction "1_1") (pintype "passive"))
      (node (ref "U2") (pin "15") (pinfunction "VCC_15") (pintype "power_in"))
      (node (ref "U2") (pin "16") (pinfunction "~{FORCEOFF}_16") (pintype "input"))
      (node (ref "U3") (pin "18") (pinfunction "AVCC_18") (pintype "bidirectional"))
      (node (ref "U3") (pin "20") (pinfunction "AREF_20") (pintype "bidirectional"))
      (node (ref "U3") (pin "4") (pinfunction "VCC_4") (pintype "bidirectional"))
      (node (ref "U3") (pin "6") (pinfunction "VCC_6") (pintype "bidirectional"))
      (node (ref "U4") (pin "18") (pinfunction "AVCC_18") (pintype "bidirectional"))
      (node (ref "U4") (pin "20") (pinfunction "AREF_20") (pintype "bidirectional"))
      (node (ref "U4") (pin "4") (pinfunction "VCC_4") (pintype "bidirectional"))
      (node (ref "U4") (pin "6") (pinfunction "VCC_6") (pintype "bidirectional"))
      (node (ref "U5") (pin "15") (pinfunction "VCC_15") (pintype "power_in"))
      (node (ref "U5") (pin "16") (pinfunction "~{FORCEOFF}_16") (pintype "input"))
      (node (ref "U6") (pin "18") (pinfunction "AVCC_18") (pintype "bidirectional"))
      (node (ref "U6") (pin "20") (pinfunction "AREF_20") (pintype "bidirectional"))
      (node (ref "U6") (pin "4") (pinfunction "VCC_4") (pintype "bidirectional"))
      (node (ref "U6") (pin "6") (pinfunction "VCC_6") (pintype "bidirectional"))
    )
    (net (code "2") (name "AREF") (class "Default")
      (node (ref "T1") (pin "AREF") (pinfunction "AREF_AREF") (pintype "power_in"))
    )
    (net (code "3") (name "ATMEG1_RESET") (class "Default")
      (node (ref "ISP1") (pin "5") (pinfunction "RST_5") (pintype "output"))
      (node (ref "R9") (pin "1") (pinfunction "1_1") (pintype "passive"))
      (node (ref "S1") (pin "P$3") (pinfunction "P$2_P$3") (pintype "bidirectional"))
      (node (ref "S1") (pin "P$4") (pinfunction "P$2_P$4") (pintype "bidirectional"))
      (node (ref "U3") (pin "29") (pinfunction "PC6(/RESET)_29") (pintype "bidirectional"))
    )
    (net (code "4") (name "ATMEG2_RESET") (class "Default")
      (node (ref "ISP2") (pin "5") (pinfunction "RST_5") (pintype "output"))
      (node (ref "R14") (pin "1") (pinfunction "1_1") (pintype "passive"))
      (node (ref "S2") (pin "P$3") (pinfunction "P$2_P$3") (pintype "bidirectional"))
      (node (ref "S2") (pin "P$4") (pinfunction "P$2_P$4") (pintype "bidirectional"))
      (node (ref "U4") (pin "29") (pinfunction "PC6(/RESET)_29") (pintype "bidirectional"))
    )
    (net (code "5") (name "ATMEG3_RESET") (class "Default")
      (node (ref "ISP3") (pin "5") (pinfunction "RST_5") (pintype "output"))
      (node (ref "R22") (pin "1") (pinfunction "1_1") (pintype "passive"))
      (node (ref "U6") (pin "29") (pinfunction "PC6(/RESET)_29") (pintype "bidirectional"))
    )
    (net (code "6") (name "AUX5") (class "Default")
      (node (ref "C17") (pin "+") (pinfunction "+_+") (pintype "passive"))
      (node (ref "C21") (pin "+") (pinfunction "+_+") (pintype "passive"))
      (node (ref "C22") (pin "1") (pinfunction "1_1") (pintype "passive"))
      (node (ref "C23") (pin "1") (pinfunction "1_1") (pintype "passive"))
      (node (ref "CAN1") (pin "5V") (pinfunction "+5V_5V") (pintype "bidirectional"))
      (node (ref "CAN1") (pin "VCC") (pinfunction "VCC_VCC") (pintype "bidirectional"))
      (node (ref "D3") (pin "P$1") (pinfunction "P$1_P$1") (pintype "bidirectional"))
      (node (ref "E1") (pin "3") (pinfunction "3_3") (pintype "bidirectional"))
      (node (ref "E1") (pin "4") (pinfunction "4_4") (pintype "bidirectional"))
      (node (ref "F10") (pin "1") (pinfunction "1_1") (pintype "passive"))
    )
    (net (code "7") (name "AUX12") (class "Default")
      (node (ref "ETH1") (pin "P$5") (pinfunction "5_P$5") (pintype "bidirectional"))
      (node (ref "ETH6") (pin "P$1") (pinfunction "1_P$1") (pintype "bidirectional"))
      (node (ref "F4") (pin "1") (pinfunction "1_1") (pintype "passive"))
      (node (ref "F9") (pin "1") (pinfunction "1_1") (pintype "passive"))
    )
    (net (code "8") (name "CAPCURR") (class "Default")
      (node (ref "ETH2") (pin "P$1") (pinfunction "1_P$1") (pintype "bidirectional"))
      (node (ref "R5") (pin "1") (pinfunction "1_1") (pintype "passive"))
      (node (ref "T1") (pin "17/A3") (pinfunction "17/A3/T_17/A3") (pintype "bidirectional"))
    )
    (net (code "9") (name "CAPVOLT") (class "Default")
      (node (ref "ETH2") (pin "P$3") (pinfunction "3_P$3") (pintype "bidirectional"))
      (node (ref "R7") (pin "1") (pinfunction "1_1") (pintype "passive"))
      (node (ref "T1") (pin "14/A0") (pinfunction "14/A0_14/A0") (pintype "bidirectional"))
    )
    (net (code "10") (name "CAP_R") (class "Default")
      (node (ref "IC1") (pin "8") (pinfunction "I0_8") (pintype "input"))
      (node (ref "T1") (pin "11") (pinfunction "11/MOSI_11") (pintype "bidirectional"))
    )
    (net (code "11") (name "CAP_R_OUT") (class "Default")
      (node (ref "ETH1") (pin "P$3") (pinfunction "3_P$3") (pintype "bidirectional"))
      (node (ref "IC1") (pin "10") (pinfunction "O_10") (pintype "output"))
    )
    (net (code "12") (name "CHARGE_R") (class "Default")
      (node (ref "IC1") (pin "12") (pinfunction "I0_12") (pintype "input"))
      (node (ref "T1") (pin "12") (pinfunction "12/MISO_12") (pintype "bidirectional"))
    )
    (net (code "13") (name "CHARGE_R_OUT") (class "Default")
      (node (ref "ETH1") (pin "P$4") (pinfunction "4_P$4") (pintype "bidirectional"))
      (node (ref "IC1") (pin "11") (pinfunction "O_11") (pintype "output"))
    )
    (net (code "14") (name "CVMRX") (class "Default")
      (node (ref "U2") (pin "9") (pinfunction "ROUT_9") (pintype "output"))
      (node (ref "U3") (pin "30") (pinfunction "PD0(RXD)_30") (pintype "bidirectional"))
    )
    (net (code "15") (name "CVMRX12") (class "Default")
      (node (ref "ETH3") (pin "P$3") (pinfunction "3_P$3") (pintype "bidirectional"))
      (node (ref "U2") (pin "8") (pinfunction "RIN_8") (pintype "input"))
    )
    (net (code "16") (name "CVMSIG1") (class "Default")
      (node (ref "ETH3") (pin "P$5") (pinfunction "5_P$5") (pintype "bidirectional"))
      (node (ref "R13") (pin "2") (pinfunction "2_2") (pintype "passive"))
      (node (ref "U1") (pin "6") (pinfunction "1C0_6") (pintype "input"))
    )
    (net (code "17") (name "CVMSIG2") (class "Default")
      (node (ref "ETH3") (pin "P$6") (pinfunction "6_P$6") (pintype "bidirectional"))
      (node (ref "R12") (pin "2") (pinfunction "2_2") (pintype "passive"))
      (node (ref "U1") (pin "5") (pinfunction "1C1_5") (pintype "input"))
    )
    (net (code "18") (name "CVMSIG3") (class "Default")
      (node (ref "ETH3") (pin "P$7") (pinfunction "7_P$7") (pintype "bidirectional"))
      (node (ref "R11") (pin "2") (pinfunction "2_2") (pintype "passive"))
      (node (ref "U1") (pin "4") (pinfunction "1C2_4") (pintype "input"))
    )
    (net (code "19") (name "CVMSIG4") (class "Default")
      (node (ref "ETH3") (pin "P$8") (pinfunction "8_P$8") (pintype "bidirectional"))
      (node (ref "R10") (pin "2") (pinfunction "2_2") (pintype "passive"))
      (node (ref "U1") (pin "3") (pinfunction "1C3_3") (pintype "input"))
    )
    (net (code "20") (name "CVMTX") (class "Default")
      (node (ref "U2") (pin "11") (pinfunction "DIN_11") (pintype "input"))
      (node (ref "U3") (pin "31") (pinfunction "PD1(TXD)_31") (pintype "bidirectional"))
    )
    (net (code "21") (name "CVMTX12") (class "Default")
      (node (ref "ETH3") (pin "P$2") (pinfunction "2_P$2") (pintype "bidirectional"))
      (node (ref "U2") (pin "13") (pinfunction "DOUT_13") (pintype "output"))
    )
    (net (code "22") (name "CVM_SER_INVALID") (class "Default")
      (node (ref "U2") (pin "10") (pinfunction "~{INVALID}_10") (pintype "output"))
      (node (ref "U3") (pin "1") (pinfunction "PD3(INT1)_1") (pintype "bidirectional"))
    )
    (net (code "23") (name "EXTRA_SIG") (class "Default")
      (node (ref "ETH7") (pin "P$2") (pinfunction "2_P$2") (pintype "bidirectional"))
      (node (ref "R21") (pin "2") (pinfunction "2_2") (pintype "passive"))
      (node (ref "U1") (pin "11") (pinfunction "2C1_11") (pintype "input"))
    )
    (net (code "24") (name "EXTRA_V") (class "Default")
      (node (ref "M1") (pin "IN3") (pinfunction "IN3_IN3") (pintype "bidirectional"))
      (node (ref "T1") (pin "10") (pinfunction "10/TX2/PWM_10") (pintype "bidirectional"))
    )
    (net (code "25") (name "EXTRA_V_G") (class "Default")
      (node (ref "ETH6") (pin "P$6") (pinfunction "6_P$6") (pintype "bidirectional"))
      (node (ref "M1") (pin "OUT3") (pinfunction "OUT3_OUT3") (pintype "bidirectional"))
      (node (ref "R15") (pin "2") (pinfunction "2_2") (pintype "passive"))
    )
    (net (code "26") (name "FC5") (class "Default")
      (node (ref "C18") (pin "+") (pinfunction "+_+") (pintype "passive"))
      (node (ref "C24") (pin "1") (pinfunction "1_1") (pintype "passive"))
      (node (ref "C25") (pin "+") (pinfunction "+_+") (pintype "passive"))
      (node (ref "C26") (pin "1") (pinfunction "1_1") (pintype "passive"))
      (node (ref "D2") (pin "P$1") (pinfunction "P$1_P$1") (pintype "bidirectional"))
      (node (ref "ETH2") (pin "P$5") (pinfunction "5_P$5") (pintype "bidirectional"))
      (node (ref "F2") (pin "2") (pinfunction "2_2") (pintype "passive"))
      (node (ref "F3") (pin "1") (pinfunction "1_1") (pintype "passive"))
      (node (ref "F6") (pin "1") (pinfunction "1_1") (pintype "passive"))
      (node (ref "F7") (pin "1") (pinfunction "1_1") (pintype "passive"))
      (node (ref "M1") (pin "VDD") (pinfunction "V+_VDD") (pintype "bidirectional"))
      (node (ref "O1") (pin "P$4") (pinfunction "RAW_P$4") (pintype "bidirectional"))
      (node (ref "U1") (pin "16") (pinfunction "VCC_16") (pintype "power_in"))
    )
    (net (code "27") (name "FC12") (class "Default")
      (node (ref "ETH1") (pin "P$6") (pinfunction "6_P$6") (pintype "bidirectional"))
      (node (ref "ETH5") (pin "P$1") (pinfunction "1_P$1") (pintype "bidirectional"))
      (node (ref "ETH6") (pin "P$3") (pinfunction "3_P$3") (pintype "bidirectional"))
      (node (ref "ETH6") (pin "P$5") (pinfunction "5_P$5") (pintype "bidirectional"))
      (node (ref "F5") (pin "1") (pinfunction "1_1") (pintype "passive"))
      (node (ref "F8") (pin "1") (pinfunction "1_1") (pintype "passive"))
    )
    (net (code "28") (name "FCCURR") (class "Default")
      (node (ref "ETH2") (pin "P$2") (pinfunction "2_P$2") (pintype "bidirectional"))
      (node (ref "R6") (pin "1") (pinfunction "1_1") (pintype "passive"))
      (node (ref "T1") (pin "15/A1") (pinfunction "15/A1/T_15/A1") (pintype "bidirectional"))
    )
    (net (code "29") (name "FCC_R") (class "Default")
      (node (ref "ETH2") (pin "P$6") (pinfunction "6_P$6") (pintype "bidirectional"))
      (node (ref "T1") (pin "20/A6") (pinfunction "20/A6/PWM_20/A6") (pintype "bidirectional"))
    )
    (net (code "30") (name "FCPRES") (class "Default")
      (node (ref "R18") (pin "2") (pinfunction "2_2") (pintype "passive"))
      (node (ref "R19") (pin "2") (pinfunction "2_2") (pintype "passive"))
      (node (ref "T1") (pin "A11") (pinfunction "A11_A11") (pintype "bidirectional"))
    )
    (net (code "31") (name "FCVOLT") (class "Default")
      (node (ref "ETH2") (pin "P$4") (pinfunction "4_P$4") (pintype "bidirectional"))
      (node (ref "R8") (pin "1") (pinfunction "1_1") (pintype "passive"))
      (node (ref "T1") (pin "16/A2") (pinfunction "16/A2/T_16/A2") (pintype "bidirectional"))
    )
    (net (code "32") (name "GND") (class "Default")
      (node (ref "C10") (pin "2") (pinfunction "2_2") (pintype "passive"))
      (node (ref "C11") (pin "2") (pinfunction "2_2") (pintype "passive"))
      (node (ref "C12") (pin "2") (pinfunction "2_2") (pintype "passive"))
      (node (ref "C14") (pin "2") (pinfunction "2_2") (pintype "passive"))
      (node (ref "C15") (pin "2") (pinfunction "2_2") (pintype "passive"))
      (node (ref "C17") (pin "-") (pinfunction "-_-") (pintype "passive"))
      (node (ref "C18") (pin "-") (pinfunction "-_-") (pintype "passive"))
      (node (ref "C19") (pin "2") (pinfunction "2_2") (pintype "passive"))
      (node (ref "C2") (pin "2") (pinfunction "2_2") (pintype "passive"))
      (node (ref "C20") (pin "2") (pinfunction "2_2") (pintype "passive"))
      (node (ref "C21") (pin "-") (pinfunction "-_-") (pintype "passive"))
      (node (ref "C22") (pin "2") (pinfunction "2_2") (pintype "passive"))
      (node (ref "C23") (pin "2") (pinfunction "2_2") (pintype "passive"))
      (node (ref "C24") (pin "2") (pinfunction "2_2") (pintype "passive"))
      (node (ref "C25") (pin "-") (pinfunction "-_-") (pintype "passive"))
      (node (ref "C26") (pin "2") (pinfunction "2_2") (pintype "passive"))
      (node (ref "C3") (pin "2") (pinfunction "2_2") (pintype "passive"))
      (node (ref "C4") (pin "2") (pinfunction "2_2") (pintype "passive"))
      (node (ref "C5") (pin "2") (pinfunction "2_2") (pintype "passive"))
      (node (ref "C7") (pin "2") (pinfunction "2_2") (pintype "passive"))
      (node (ref "C8") (pin "2") (pinfunction "2_2") (pintype "passive"))
      (node (ref "C9") (pin "2") (pinfunction "2_2") (pintype "passive"))
      (node (ref "CAN1") (pin "GND") (pinfunction "GND_GND") (pintype "bidirectional"))
      (node (ref "CAN1") (pin "GND_") (pinfunction "GND__GND_") (pintype "bidirectional"))
      (node (ref "D1") (pin "A") (pinfunction "A_A") (pintype "passive"))
      (node (ref "D2") (pin "P$2") (pinfunction "P$2_P$2") (pintype "bidirectional"))
      (node (ref "D3") (pin "P$2") (pinfunction "P$2_P$2") (pintype "bidirectional"))
      (node (ref "E1") (pin "5") (pinfunction "5_5") (pintype "bidirectional"))
      (node (ref "E1") (pin "6") (pinfunction "6_6") (pintype "bidirectional"))
      (node (ref "E1") (pin "SH1") (pinfunction "SH1_SH1") (pintype "bidirectional"))
      (node (ref "E1") (pin "SH2") (pinfunction "SH2_SH2") (pintype "bidirectional"))
      (node (ref "E2") (pin "5") (pinfunction "5_5") (pintype "bidirectional"))
      (node (ref "E2") (pin "6") (pinfunction "6_6") (pintype "bidirectional"))
      (node (ref "E2") (pin "SH1") (pinfunction "SH1_SH1") (pintype "bidirectional"))
      (node (ref "E2") (pin "SH2") (pinfunction "SH2_SH2") (pintype "bidirectional"))
      (node (ref "ETH1") (pin "P$13") (pinfunction "SHD1_P$13") (pintype "bidirectional"))
      (node (ref "ETH1") (pin "P$14") (pinfunction "SHD2_P$14") (pintype "bidirectional"))
      (node (ref "ETH1") (pin "P$7") (pinfunction "7_P$7") (pintype "bidirectional"))
      (node (ref "ETH1") (pin "P$8") (pinfunction "8_P$8") (pintype "bidirectional"))
      (node (ref "ETH2") (pin "P$13") (pinfunction "SHD1_P$13") (pintype "bidirectional"))
      (node (ref "ETH2") (pin "P$14") (pinfunction "SHD2_P$14") (pintype "bidirectional"))
      (node (ref "ETH2") (pin "P$7") (pinfunction "7_P$7") (pintype "bidirectional"))
      (node (ref "ETH2") (pin "P$8") (pinfunction "8_P$8") (pintype "bidirectional"))
      (node (ref "ETH3") (pin "P$13") (pinfunction "SHD1_P$13") (pintype "bidirectional"))
      (node (ref "ETH3") (pin "P$14") (pinfunction "SHD2_P$14") (pintype "bidirectional"))
      (node (ref "ETH3") (pin "P$4") (pinfunction "4_P$4") (pintype "bidirectional"))
      (node (ref "ETH4") (pin "P$13") (pinfunction "SHD1_P$13") (pintype "bidirectional"))
      (node (ref "ETH4") (pin "P$14") (pinfunction "SHD2_P$14") (pintype "bidirectional"))
      (node (ref "ETH4") (pin "P$8") (pinfunction "8_P$8") (pintype "bidirectional"))
      (node (ref "ETH5") (pin "P$13") (pinfunction "SHD1_P$13") (pintype "bidirectional"))
      (node (ref "ETH5") (pin "P$14") (pinfunction "SHD2_P$14") (pintype "bidirectional"))
      (node (ref "ETH5") (pin "P$2") (pinfunction "2_P$2") (pintype "bidirectional"))
      (node (ref "ETH6") (pin "P$13") (pinfunction "SHD1_P$13") (pintype "bidirectional"))
      (node (ref "ETH6") (pin "P$14") (pinfunction "SHD2_P$14") (pintype "bidirectional"))
      (node (ref "ETH7") (pin "P$13") (pinfunction "SHD1_P$13") (pintype "bidirectional"))
      (node (ref "ETH7") (pin "P$14") (pinfunction "SHD2_P$14") (pintype "bidirectional"))
      (node (ref "ETH7") (pin "P$5") (pinfunction "5_P$5") (pintype "bidirectional"))
      (node (ref "FAN1") (pin "GND") (pinfunction "GND_GND") (pintype "bidirectional"))
      (node (ref "FAN1") (pin "GND2") (pinfunction "GND_GND2") (pintype "bidirectional"))
      (node (ref "FAN1") (pin "GND3") (pinfunction "GND_GND3") (pintype "bidirectional"))
      (node (ref "ISP1") (pin "6") (pinfunction "GND_6") (pintype "power_in"))
      (node (ref "ISP2") (pin "6") (pinfunction "GND_6") (pintype "power_in"))
      (node (ref "ISP3") (pin "6") (pinfunction "GND_6") (pintype "power_in"))
      (node (ref "LCD1") (pin "GND1") (pinfunction "GND_GND1") (pintype "bidirectional"))
      (node (ref "LCD1") (pin "GND10") (pinfunction "GND_GND10") (pintype "bidirectional"))
      (node (ref "LCD1") (pin "GND11") (pinfunction "GND_GND11") (pintype "bidirectional"))
      (node (ref "LCD1") (pin "GND12") (pinfunction "GND_GND12") (pintype "bidirectional"))
      (node (ref "LCD1") (pin "GND13") (pinfunction "GND_GND13") (pintype "bidirectional"))
      (node (ref "LCD1") (pin "GND2") (pinfunction "GND_GND2") (pintype "bidirectional"))
      (node (ref "LCD1") (pin "GND3") (pinfunction "GND_GND3") (pintype "bidirectional"))
      (node (ref "LCD1") (pin "GND4") (pinfunction "GND_GND4") (pintype "bidirectional"))
      (node (ref "LCD1") (pin "GND5") (pinfunction "GND_GND5") (pintype "bidirectional"))
      (node (ref "LCD1") (pin "GND6") (pinfunction "GND_GND6") (pintype "bidirectional"))
      (node (ref "LCD1") (pin "GND7") (pinfunction "GND_GND7") (pintype "bidirectional"))
      (node (ref "LCD1") (pin "GND8") (pinfunction "GND_GND8") (pintype "bidirectional"))
      (node (ref "LCD1") (pin "GND9") (pinfunction "GND_GND9") (pintype "bidirectional"))
      (node (ref "LED1") (pin "C") (pinfunction "C_C") (pintype "passive"))
      (node (ref "LED10") (pin "C") (pinfunction "C_C") (pintype "passive"))
      (node (ref "LED11") (pin "C") (pinfunction "C_C") (pintype "passive"))
      (node (ref "LED12") (pin "C") (pinfunction "C_C") (pintype "passive"))
      (node (ref "LED2") (pin "C") (pinfunction "C_C") (pintype "passive"))
      (node (ref "LED3") (pin "C") (pinfunction "C_C") (pintype "passive"))
      (node (ref "LED4") (pin "C") (pinfunction "C_C") (pintype "passive"))
      (node (ref "LED5") (pin "C") (pinfunction "C_C") (pintype "passive"))
      (node (ref "LED6") (pin "C") (pinfunction "C_C") (pintype "passive"))
      (node (ref "LED7") (pin "C") (pinfunction "C_C") (pintype "passive"))
      (node (ref "LED8") (pin "C") (pinfunction "C_C") (pintype "passive"))
      (node (ref "LED9") (pin "C") (pinfunction "C_C") (pintype "passive"))
      (node (ref "M1") (pin "GND") (pinfunction "GND_GND") (pintype "bidirectional"))
      (node (ref "M1") (pin "GND1") (pinfunction "GND_GND1") (pintype "bidirectional"))
      (node (ref "M1") (pin "GND2") (pinfunction "GND_GND2") (pintype "bidirectional"))
      (node (ref "M1") (pin "VSS") (pinfunction "GND_VSS") (pintype "bidirectional"))
      (node (ref "O1") (pin "P$5") (pinfunction "GND_P$5") (pintype "bidirectional"))
      (node (ref "O1") (pin "P$6") (pinfunction "GND2_P$6") (pintype "bidirectional"))
      (node (ref "R1") (pin "2") (pinfunction "2_2") (pintype "passive"))
      (node (ref "R10") (pin "1") (pinfunction "1_1") (pintype "passive"))
      (node (ref "R11") (pin "1") (pinfunction "1_1") (pintype "passive"))
      (node (ref "R12") (pin "1") (pinfunction "1_1") (pintype "passive"))
      (node (ref "R13") (pin "1") (pinfunction "1_1") (pintype "passive"))
      (node (ref "R15") (pin "1") (pinfunction "1_1") (pintype "passive"))
      (node (ref "R16") (pin "1") (pinfunction "1_1") (pintype "passive"))
      (node (ref "R17") (pin "1") (pinfunction "1_1") (pintype "passive"))
      (node (ref "R18") (pin "1") (pinfunction "1_1") (pintype "passive"))
      (node (ref "R2") (pin "1") (pinfunction "1_1") (pintype "passive"))
      (node (ref "R20") (pin "1") (pinfunction "1_1") (pintype "passive"))
      (node (ref "R21") (pin "1") (pinfunction "1_1") (pintype "passive"))
      (node (ref "R7") (pin "2") (pinfunction "2_2") (pintype "passive"))
      (node (ref "R8") (pin "2") (pinfunction "2_2") (pintype "passive"))
      (node (ref "RTC1") (pin "P$2") (pinfunction "GND_P$2") (pintype "bidirectional"))
      (node (ref "S1") (pin "P$1") (pinfunction "P$1_P$1") (pintype "bidirectional"))
      (node (ref "S1") (pin "P$2") (pinfunction "P$1_P$2") (pintype "bidirectional"))
      (node (ref "S2") (pin "P$1") (pinfunction "P$1_P$1") (pintype "bidirectional"))
      (node (ref "S2") (pin "P$2") (pinfunction "P$1_P$2") (pintype "bidirectional"))
      (node (ref "SHT1") (pin "GND") (pinfunction "GND_GND") (pintype "bidirectional"))
      (node (ref "SJ1") (pin "1") (pinfunction "1_1") (pintype "passive"))
      (node (ref "T1") (pin "AGND") (pinfunction "AGND_AGND") (pintype "power_in"))
      (node (ref "T1") (pin "GND") (pinfunction "GND_GND") (pintype "power_in"))
      (node (ref "T1") (pin "GND1") (pinfunction "GND_GND1") (pintype "power_in"))
      (node (ref "U1") (pin "1") (pinfunction "1~{G}_1") (pintype "input"))
      (node (ref "U1") (pin "15") (pinfunction "2~{G}_15") (pintype "input"))
      (node (ref "U1") (pin "8") (pinfunction "GND_8") (pintype "passive"))
      (node (ref "U2") (pin "1") (pinfunction "~{EN}_1") (pintype "input"))
      (node (ref "U2") (pin "12") (pinfunction "FORCEON_12") (pintype "input"))
      (node (ref "U2") (pin "14") (pinfunction "GND_14") (pintype "passive"))
      (node (ref "U3") (pin "21") (pinfunction "AGND_21") (pintype "bidirectional"))
      (node (ref "U3") (pin "3") (pinfunction "GND_3") (pintype "bidirectional"))
      (node (ref "U3") (pin "5") (pinfunction "GND_5") (pintype "bidirectional"))
      (node (ref "U4") (pin "21") (pinfunction "AGND_21") (pintype "bidirectional"))
      (node (ref "U4") (pin "3") (pinfunction "GND_3") (pintype "bidirectional"))
      (node (ref "U4") (pin "5") (pinfunction "GND_5") (pintype "bidirectional"))
      (node (ref "U5") (pin "1") (pinfunction "~{EN}_1") (pintype "input"))
      (node (ref "U5") (pin "12") (pinfunction "FORCEON_12") (pintype "input"))
      (node (ref "U5") (pin "14") (pinfunction "GND_14") (pintype "passive"))
      (node (ref "U6") (pin "21") (pinfunction "AGND_21") (pintype "bidirectional"))
      (node (ref "U6") (pin "3") (pinfunction "GND_3") (pintype "bidirectional"))
      (node (ref "U6") (pin "5") (pinfunction "GND_5") (pintype "bidirectional"))
    )
    (net (code "33") (name "H2_OK") (class "Default")
      (node (ref "ETH7") (pin "P$1") (pinfunction "1_P$1") (pintype "bidirectional"))
      (node (ref "IC1") (pin "13") (pinfunction "I1_13") (pintype "input"))
      (node (ref "IC1") (pin "2") (pinfunction "I1_2") (pintype "input"))
      (node (ref "IC1") (pin "6") (pinfunction "I1_6") (pintype "input"))
      (node (ref "IC1") (pin "9") (pinfunction "I1_9") (pintype "input"))
      (node (ref "M1") (pin "ESTOP") (pinfunction "ESTOP_ESTOP") (pintype "bidirectional"))
      (node (ref "R20") (pin "2") (pinfunction "2_2") (pintype "passive"))
      (node (ref "U1") (pin "10") (pinfunction "2C0_10") (pintype "input"))
    )
    (net (code "34") (name "MISO1") (class "Default")
      (node (ref "ISP1") (pin "1") (pinfunction "MISO_1") (pintype "input"))
      (node (ref "U3") (pin "16") (pinfunction "PB4(MISO)_16") (pintype "bidirectional"))
    )
    (net (code "35") (name "MISO2") (class "Default")
      (node (ref "ISP2") (pin "1") (pinfunction "MISO_1") (pintype "input"))
      (node (ref "U4") (pin "16") (pinfunction "PB4(MISO)_16") (pintype "bidirectional"))
    )
    (net (code "36") (name "MISO3") (class "Default")
      (node (ref "ISP3") (pin "1") (pinfunction "MISO_1") (pintype "input"))
      (node (ref "U6") (pin "16") (pinfunction "PB4(MISO)_16") (pintype "bidirectional"))
    )
    (net (code "37") (name "MOSI1") (class "Default")
      (node (ref "ISP1") (pin "4") (pinfunction "MOSI_4") (pintype "output"))
      (node (ref "U3") (pin "15") (pinfunction "PB3(MOSI/OC2)_15") (pintype "bidirectional"))
    )
    (net (code "38") (name "MOSI2") (class "Default")
      (node (ref "ISP2") (pin "4") (pinfunction "MOSI_4") (pintype "output"))
      (node (ref "U4") (pin "15") (pinfunction "PB3(MOSI/OC2)_15") (pintype "bidirectional"))
    )
    (net (code "39") (name "MOSI3") (class "Default")
      (node (ref "ISP3") (pin "4") (pinfunction "MOSI_4") (pintype "output"))
      (node (ref "U6") (pin "15") (pinfunction "PB3(MOSI/OC2)_15") (pintype "bidirectional"))
    )
    (net (code "40") (name "MOTOR_R") (class "Default")
      (node (ref "IC1") (pin "5") (pinfunction "I0_5") (pintype "input"))
      (node (ref "T1") (pin "22/A8") (pinfunction "22/A8/T/PWM_22/A8") (pintype "bidirectional"))
    )
    (net (code "41") (name "MOTOR_R_OUT") (class "Default")
      (node (ref "ETH1") (pin "P$2") (pinfunction "2_P$2") (pintype "bidirectional"))
      (node (ref "IC1") (pin "4") (pinfunction "O_4") (pintype "output"))
    )
    (net (code "42") (name "MRX") (class "Default")
      (node (ref "U4") (pin "30") (pinfunction "PD0(RXD)_30") (pintype "bidirectional"))
      (node (ref "U5") (pin "9") (pinfunction "ROUT_9") (pintype "output"))
    )
    (net (code "43") (name "MRX12") (class "Default")
      (node (ref "ETH4") (pin "P$2") (pinfunction "2_P$2") (pintype "bidirectional"))
      (node (ref "U5") (pin "8") (pinfunction "RIN_8") (pintype "input"))
    )
    (net (code "44") (name "MTX") (class "Default")
      (node (ref "U4") (pin "31") (pinfunction "PD1(TXD)_31") (pintype "bidirectional"))
      (node (ref "U5") (pin "11") (pinfunction "DIN_11") (pintype "input"))
    )
    (net (code "45") (name "MTX12") (class "Default")
      (node (ref "ETH4") (pin "P$1") (pinfunction "1_P$1") (pintype "bidirectional"))
      (node (ref "U5") (pin "13") (pinfunction "DOUT_13") (pintype "output"))
    )
    (net (code "46") (name "MULTA") (class "Default")
      (node (ref "T1") (pin "3") (pinfunction "3/CAN-TX/PWM_3") (pintype "bidirectional"))
      (node (ref "U1") (pin "14") (pinfunction "A_14") (pintype "input"))
    )
    (net (code "47") (name "MULTB") (class "Default")
      (node (ref "T1") (pin "4") (pinfunction "4/CAN-RX-PWM_4") (pintype "bidirectional"))
      (node (ref "U1") (pin "2") (pinfunction "B_2") (pintype "input"))
    )
    (net (code "48") (name "MULTO1") (class "Default")
      (node (ref "R1") (pin "1") (pinfunction "1_1") (pintype "passive"))
      (node (ref "T1") (pin "5") (pinfunction "5/PWM_5") (pintype "bidirectional"))
      (node (ref "U1") (pin "7") (pinfunction "1Y_7") (pintype "output"))
    )
    (net (code "49") (name "MULTO2") (class "Default")
      (node (ref "R2") (pin "2") (pinfunction "2_2") (pintype "passive"))
      (node (ref "T1") (pin "2") (pinfunction "2_2") (pintype "bidirectional"))
      (node (ref "U1") (pin "9") (pinfunction "2Y_9") (pintype "output"))
    )
    (net (code "50") (name "M_SER_INVALID") (class "Default")
      (node (ref "U4") (pin "1") (pinfunction "PD3(INT1)_1") (pintype "bidirectional"))
      (node (ref "U5") (pin "10") (pinfunction "~{INVALID}_10") (pintype "output"))
    )
    (net (code "51") (name "M_SIG_1") (class "Default")
      (node (ref "ETH4") (pin "P$6") (pinfunction "6_P$6") (pintype "bidirectional"))
      (node (ref "U1") (pin "12") (pinfunction "2C2_12") (pintype "input"))
    )
    (net (code "52") (name "M_SIG_2") (class "Default")
      (node (ref "ETH4") (pin "P$7") (pinfunction "7_P$7") (pintype "bidirectional"))
      (node (ref "U1") (pin "13") (pinfunction "2C3_13") (pintype "input"))
    )
    (net (code "53") (name "Net-(E1-Pad1)") (class "Default")
      (node (ref "E1") (pin "1") (pinfunction "1_1") (pintype "bidirectional"))
      (node (ref "E1") (pin "2") (pinfunction "2_2") (pintype "bidirectional"))
      (node (ref "F4") (pin "2") (pinfunction "2_2") (pintype "passive"))
    )
    (net (code "54") (name "Net-(E2-Pad1)") (class "Default")
      (node (ref "E2") (pin "1") (pinfunction "1_1") (pintype "bidirectional"))
      (node (ref "E2") (pin "2") (pinfunction "2_2") (pintype "bidirectional"))
      (node (ref "F5") (pin "2") (pinfunction "2_2") (pintype "passive"))
    )
    (net (code "55") (name "Net-(E2-Pad3)") (class "Default")
      (node (ref "E2") (pin "3") (pinfunction "3_3") (pintype "bidirectional"))
      (node (ref "E2") (pin "4") (pinfunction "4_4") (pintype "bidirectional"))
      (node (ref "F6") (pin "2") (pinfunction "2_2") (pintype "passive"))
    )
    (net (code "56") (name "Net-(ETH3-1)") (class "Default")
      (node (ref "ETH3") (pin "P$1") (pinfunction "1_P$1") (pintype "bidirectional"))
      (node (ref "F3") (pin "2") (pinfunction "2_2") (pintype "passive"))
    )
    (net (code "57") (name "Net-(ETH5-3)") (class "Default")
      (node (ref "ETH5") (pin "P$3") (pinfunction "3_P$3") (pintype "bidirectional"))
      (node (ref "R19") (pin "1") (pinfunction "1_1") (pintype "passive"))
    )
    (net (code "58") (name "Net-(ETH7-6)") (class "Default")
      (node (ref "ETH7") (pin "P$6") (pinfunction "6_P$6") (pintype "bidirectional"))
      (node (ref "F9") (pin "2") (pinfunction "2_2") (pintype "passive"))
    )
    (net (code "59") (name "Net-(ETH7-8)") (class "Default")
      (node (ref "ETH7") (pin "P$8") (pinfunction "8_P$8") (pintype "bidirectional"))
      (node (ref "F10") (pin "2") (pinfunction "2_2") (pintype "passive"))
    )
    (net (code "60") (name "Net-(F1-Pad1)") (class "Default")
      (node (ref "F1") (pin "1") (pinfunction "1_1") (pintype "passive"))
      (node (ref "T1") (pin "3.3V") (pinfunction "3.3V_3.3V") (pintype "power_in"))
      (node (ref "T1") (pin "3.3V1") (pinfunction "3.3V_3.3V1") (pintype "power_in"))
    )
    (net (code "61") (name "Net-(F2-Pad1)") (class "Default")
      (node (ref "F2") (pin "1") (pinfunction "1_1") (pintype "passive"))
      (node (ref "T1") (pin "VIN") (pinfunction "VIN_VIN") (pintype "power_in"))
    )
    (net (code "62") (name "Net-(F7-Pad2)") (class "Default")
      (node (ref "F7") (pin "2") (pinfunction "2_2") (pintype "passive"))
      (node (ref "FAN1") (pin "5") (pinfunction "5V_5") (pintype "bidirectional"))
      (node (ref "FAN1") (pin "5_2") (pinfunction "5V_5_2") (pintype "bidirectional"))
    )
    (net (code "63") (name "Net-(F8-Pad2)") (class "Default")
      (node (ref "F8") (pin "2") (pinfunction "2_2") (pintype "passive"))
      (node (ref "FAN1") (pin "12") (pinfunction "12V_12") (pintype "bidirectional"))
      (node (ref "FAN1") (pin "12_2") (pinfunction "12V_12_2") (pintype "bidirectional"))
      (node (ref "FAN1") (pin "12_3") (pinfunction "12V_12_3") (pintype "bidirectional"))
    )
    (net (code "64") (name "Net-(LED1-PadA)") (class "Default")
      (node (ref "LED1") (pin "A") (pinfunction "A_A") (pintype "passive"))
      (node (ref "R23") (pin "1") (pinfunction "1_1") (pintype "passive"))
    )
    (net (code "65") (name "Net-(LED2-PadA)") (class "Default")
      (node (ref "LED2") (pin "A") (pinfunction "A_A") (pintype "passive"))
      (node (ref "R24") (pin "1") (pinfunction "1_1") (pintype "passive"))
    )
    (net (code "66") (name "Net-(LED3-PadA)") (class "Default")
      (node (ref "LED3") (pin "A") (pinfunction "A_A") (pintype "passive"))
      (node (ref "R25") (pin "1") (pinfunction "1_1") (pintype "passive"))
    )
    (net (code "67") (name "Net-(LED4-PadA)") (class "Default")
      (node (ref "LED4") (pin "A") (pinfunction "A_A") (pintype "passive"))
      (node (ref "R26") (pin "1") (pinfunction "1_1") (pintype "passive"))
    )
    (net (code "68") (name "Net-(LED5-PadA)") (class "Default")
      (node (ref "LED5") (pin "A") (pinfunction "A_A") (pintype "passive"))
      (node (ref "R27") (pin "1") (pinfunction "1_1") (pintype "passive"))
    )
    (net (code "69") (name "Net-(LED6-PadA)") (class "Default")
      (node (ref "LED6") (pin "A") (pinfunction "A_A") (pintype "passive"))
      (node (ref "R28") (pin "1") (pinfunction "1_1") (pintype "passive"))
    )
    (net (code "70") (name "Net-(LED7-PadA)") (class "Default")
      (node (ref "LED7") (pin "A") (pinfunction "A_A") (pintype "passive"))
      (node (ref "R29") (pin "1") (pinfunction "1_1") (pintype "passive"))
    )
    (net (code "71") (name "Net-(LED8-PadA)") (class "Default")
      (node (ref "LED8") (pin "A") (pinfunction "A_A") (pintype "passive"))
      (node (ref "R30") (pin "1") (pinfunction "1_1") (pintype "passive"))
    )
    (net (code "72") (name "Net-(LED9-PadA)") (class "Default")
      (node (ref "LED9") (pin "A") (pinfunction "A_A") (pintype "passive"))
      (node (ref "R31") (pin "1") (pinfunction "1_1") (pintype "passive"))
    )
    (net (code "73") (name "Net-(LED10-PadA)") (class "Default")
      (node (ref "LED10") (pin "A") (pinfunction "A_A") (pintype "passive"))
      (node (ref "R32") (pin "1") (pinfunction "1_1") (pintype "passive"))
    )
    (net (code "74") (name "Net-(LED11-PadA)") (class "Default")
      (node (ref "LED11") (pin "A") (pinfunction "A_A") (pintype "passive"))
      (node (ref "R33") (pin "1") (pinfunction "1_1") (pintype "passive"))
    )
    (net (code "75") (name "Net-(LED12-PadA)") (class "Default")
      (node (ref "LED12") (pin "A") (pinfunction "A_A") (pintype "passive"))
      (node (ref "R34") (pin "1") (pinfunction "1_1") (pintype "passive"))
    )
    (net (code "76") (name "Net-(U2-C1+)") (class "Default")
      (node (ref "C6") (pin "1") (pinfunction "1_1") (pintype "passive"))
      (node (ref "U2") (pin "2") (pinfunction "C1+_2") (pintype "passive"))
    )
    (net (code "77") (name "Net-(U2-C1-)") (class "Default")
      (node (ref "C6") (pin "2") (pinfunction "2_2") (pintype "passive"))
      (node (ref "U2") (pin "4") (pinfunction "C1-_4") (pintype "passive"))
    )
    (net (code "78") (name "Net-(U2-C2+)") (class "Default")
      (node (ref "C1") (pin "1") (pinfunction "1_1") (pintype "passive"))
      (node (ref "U2") (pin "5") (pinfunction "C2+_5") (pintype "passive"))
    )
    (net (code "79") (name "Net-(U2-C2-)") (class "Default")
      (node (ref "C1") (pin "2") (pinfunction "2_2") (pintype "passive"))
      (node (ref "U2") (pin "6") (pinfunction "C2-_6") (pintype "passive"))
    )
    (net (code "80") (name "Net-(U2-V+)") (class "Default")
      (node (ref "C3") (pin "1") (pinfunction "1_1") (pintype "passive"))
      (node (ref "U2") (pin "3") (pinfunction "V+_3") (pintype "power_in"))
    )
    (net (code "81") (name "Net-(U2-V-)") (class "Default")
      (node (ref "C4") (pin "1") (pinfunction "1_1") (pintype "passive"))
      (node (ref "U2") (pin "7") (pinfunction "V-_7") (pintype "power_in"))
    )
    (net (code "82") (name "Net-(U3-PB6(XTAL1{slash}TOSC1))") (class "Default")
      (node (ref "C7") (pin "1") (pinfunction "1_1") (pintype "passive"))
      (node (ref "U3") (pin "7") (pinfunction "PB6(XTAL1/TOSC1)_7") (pintype "bidirectional"))
      (node (ref "Y1") (pin "2") (pinfunction "2_2") (pintype "passive"))
    )
    (net (code "83") (name "Net-(U3-PB7(XTAL2{slash}TOSC2))") (class "Default")
      (node (ref "C8") (pin "1") (pinfunction "1_1") (pintype "passive"))
      (node (ref "U3") (pin "8") (pinfunction "PB7(XTAL2/TOSC2)_8") (pintype "bidirectional"))
      (node (ref "Y1") (pin "1") (pinfunction "1_1") (pintype "passive"))
    )
    (net (code "84") (name "Net-(U4-PB6(XTAL1{slash}TOSC1))") (class "Default")
      (node (ref "C11") (pin "1") (pinfunction "1_1") (pintype "passive"))
      (node (ref "U4") (pin "7") (pinfunction "PB6(XTAL1/TOSC1)_7") (pintype "bidirectional"))
      (node (ref "Y2") (pin "2") (pinfunction "2_2") (pintype "passive"))
    )
    (net (code "85") (name "Net-(U4-PB7(XTAL2{slash}TOSC2))") (class "Default")
      (node (ref "C12") (pin "1") (pinfunction "1_1") (pintype "passive"))
      (node (ref "U4") (pin "8") (pinfunction "PB7(XTAL2/TOSC2)_8") (pintype "bidirectional"))
      (node (ref "Y2") (pin "1") (pinfunction "1_1") (pintype "passive"))
    )
    (net (code "86") (name "Net-(U5-C1+)") (class "Default")
      (node (ref "C16") (pin "1") (pinfunction "1_1") (pintype "passive"))
      (node (ref "U5") (pin "2") (pinfunction "C1+_2") (pintype "passive"))
    )
    (net (code "87") (name "Net-(U5-C1-)") (class "Default")
      (node (ref "C16") (pin "2") (pinfunction "2_2") (pintype "passive"))
      (node (ref "U5") (pin "4") (pinfunction "C1-_4") (pintype "passive"))
    )
    (net (code "88") (name "Net-(U5-C2+)") (class "Default")
      (node (ref "C13") (pin "1") (pinfunction "1_1") (pintype "passive"))
      (node (ref "U5") (pin "5") (pinfunction "C2+_5") (pintype "passive"))
    )
    (net (code "89") (name "Net-(U5-C2-)") (class "Default")
      (node (ref "C13") (pin "2") (pinfunction "2_2") (pintype "passive"))
      (node (ref "U5") (pin "6") (pinfunction "C2-_6") (pintype "passive"))
    )
    (net (code "90") (name "Net-(U5-V+)") (class "Default")
      (node (ref "C14") (pin "1") (pinfunction "1_1") (pintype "passive"))
      (node (ref "U5") (pin "3") (pinfunction "V+_3") (pintype "power_in"))
    )
    (net (code "91") (name "Net-(U5-V-)") (class "Default")
      (node (ref "C15") (pin "1") (pinfunction "1_1") (pintype "passive"))
      (node (ref "U5") (pin "7") (pinfunction "V-_7") (pintype "power_in"))
    )
    (net (code "92") (name "Net-(U6-ADC6)") (class "Default")
      (node (ref "R27") (pin "2") (pinfunction "2_2") (pintype "passive"))
      (node (ref "U6") (pin "19") (pinfunction "ADC6_19") (pintype "bidirectional"))
    )
    (net (code "93") (name "Net-(U6-ADC7)") (class "Default")
      (node (ref "R28") (pin "2") (pinfunction "2_2") (pintype "passive"))
      (node (ref "U6") (pin "22") (pinfunction "ADC7_22") (pintype "bidirectional"))
    )
    (net (code "94") (name "Net-(U6-PC0(ADC0))") (class "Default")
      (node (ref "R23") (pin "2") (pinfunction "2_2") (pintype "passive"))
      (node (ref "U6") (pin "23") (pinfunction "PC0(ADC0)_23") (pintype "bidirectional"))
    )
    (net (code "95") (name "Net-(U6-PC1(ADC1))") (class "Default")
      (node (ref "R24") (pin "2") (pinfunction "2_2") (pintype "passive"))
      (node (ref "U6") (pin "24") (pinfunction "PC1(ADC1)_24") (pintype "bidirectional"))
    )
    (net (code "96") (name "Net-(U6-PC2(ADC2))") (class "Default")
      (node (ref "R25") (pin "2") (pinfunction "2_2") (pintype "passive"))
      (node (ref "U6") (pin "25") (pinfunction "PC2(ADC2)_25") (pintype "bidirectional"))
    )
    (net (code "97") (name "Net-(U6-PC3(ADC3))") (class "Default")
      (node (ref "R26") (pin "2") (pinfunction "2_2") (pintype "passive"))
      (node (ref "U6") (pin "26") (pinfunction "PC3(ADC3)_26") (pintype "bidirectional"))
    )
    (net (code "98") (name "Net-(U6-PD0(RXD))") (class "Default")
      (node (ref "R29") (pin "2") (pinfunction "2_2") (pintype "passive"))
      (node (ref "U6") (pin "30") (pinfunction "PD0(RXD)_30") (pintype "bidirectional"))
    )
    (net (code "99") (name "Net-(U6-PD1(TXD))") (class "Default")
      (node (ref "R30") (pin "2") (pinfunction "2_2") (pintype "passive"))
      (node (ref "U6") (pin "31") (pinfunction "PD1(TXD)_31") (pintype "bidirectional"))
    )
    (net (code "100") (name "Net-(U6-PD2(INT0))") (class "Default")
      (node (ref "R31") (pin "2") (pinfunction "2_2") (pintype "passive"))
      (node (ref "U6") (pin "32") (pinfunction "PD2(INT0)_32") (pintype "bidirectional"))
    )
    (net (code "101") (name "Net-(U6-PD3(INT1))") (class "Default")
      (node (ref "R32") (pin "2") (pinfunction "2_2") (pintype "passive"))
      (node (ref "U6") (pin "1") (pinfunction "PD3(INT1)_1") (pintype "bidirectional"))
    )
    (net (code "102") (name "Net-(U6-PD4(XCK{slash}T0))") (class "Default")
      (node (ref "R33") (pin "2") (pinfunction "2_2") (pintype "passive"))
      (node (ref "U6") (pin "2") (pinfunction "PD4(XCK/T0)_2") (pintype "bidirectional"))
    )
    (net (code "103") (name "Net-(U6-PD5(T1))") (class "Default")
      (node (ref "R34") (pin "2") (pinfunction "2_2") (pintype "passive"))
      (node (ref "U6") (pin "9") (pinfunction "PD5(T1)_9") (pintype "bidirectional"))
    )
    (net (code "104") (name "PURGE_V") (class "Default")
      (node (ref "M1") (pin "IN2") (pinfunction "IN2_IN2") (pintype "bidirectional"))
      (node (ref "T1") (pin "9") (pinfunction "9/RX2/PWM_9") (pintype "bidirectional"))
    )
    (net (code "105") (name "PURGE_V_G") (class "Default")
      (node (ref "ETH6") (pin "P$4") (pinfunction "4_P$4") (pintype "bidirectional"))
      (node (ref "M1") (pin "OUT2") (pinfunction "OUT2_OUT2") (pintype "bidirectional"))
      (node (ref "R16") (pin "2") (pinfunction "2_2") (pintype "passive"))
    )
    (net (code "106") (name "RX1") (class "Default")
      (node (ref "CAN1") (pin "TX0") (pinfunction "TX0_TX0") (pintype "bidirectional"))
      (node (ref "T1") (pin "0") (pinfunction "0/RX1/T_0") (pintype "bidirectional"))
    )
    (net (code "107") (name "RX3") (class "Default")
      (node (ref "O1") (pin "P$3") (pinfunction "TXO_P$3") (pintype "bidirectional"))
      (node (ref "T1") (pin "7") (pinfunction "7/RX3_7") (pintype "bidirectional"))
    )
    (net (code "108") (name "SCK1") (class "Default")
      (node (ref "ISP1") (pin "3") (pinfunction "SCK_3") (pintype "output"))
      (node (ref "U3") (pin "17") (pinfunction "PB5(SCK)_17") (pintype "bidirectional"))
    )
    (net (code "109") (name "SCK2") (class "Default")
      (node (ref "ISP2") (pin "3") (pinfunction "SCK_3") (pintype "output"))
      (node (ref "U4") (pin "17") (pinfunction "PB5(SCK)_17") (pintype "bidirectional"))
    )
    (net (code "110") (name "SCK3") (class "Default")
      (node (ref "ISP3") (pin "3") (pinfunction "SCK_3") (pintype "output"))
      (node (ref "U6") (pin "17") (pinfunction "PB5(SCK)_17") (pintype "bidirectional"))
    )
    (net (code "111") (name "SCL") (class "Default")
      (node (ref "FAN1") (pin "SCL") (pinfunction "SCL_SCL") (pintype "bidirectional"))
      (node (ref "LCD1") (pin "SCL") (pinfunction "SCL_SCL") (pintype "bidirectional"))
      (node (ref "R3") (pin "2") (pinfunction "2_2") (pintype "passive"))
      (node (ref "RTC1") (pin "P$3") (pinfunction "SCL_P$3") (pintype "bidirectional"))
      (node (ref "SHT1") (pin "SCL") (pinfunction "SCL_SCL") (pintype "bidirectional"))
      (node (ref "T1") (pin "19/A5") (pinfunction "19/A5/T/SCL0_19/A5") (pintype "bidirectional"))
      (node (ref "U3") (pin "28") (pinfunction "PC5(ADC5/SCL)_28") (pintype "bidirectional"))
      (node (ref "U4") (pin "28") (pinfunction "PC5(ADC5/SCL)_28") (pintype "bidirectional"))
      (node (ref "U6") (pin "28") (pinfunction "PC5(ADC5/SCL)_28") (pintype "bidirectional"))
    )
    (net (code "112") (name "SDA") (class "Default")
      (node (ref "FAN1") (pin "SDA") (pinfunction "SDA_SDA") (pintype "bidirectional"))
      (node (ref "LCD1") (pin "SDA") (pinfunction "SDA_SDA") (pintype "bidirectional"))
      (node (ref "R4") (pin "2") (pinfunction "2_2") (pintype "passive"))
      (node (ref "RTC1") (pin "P$4") (pinfunction "SDA_P$4") (pintype "bidirectional"))
      (node (ref "SHT1") (pin "SDA") (pinfunction "SDA_SDA") (pintype "bidirectional"))
      (node (ref "T1") (pin "18/A4") (pinfunction "18/A4/T/SDA0_18/A4") (pintype "bidirectional"))
      (node (ref "U3") (pin "27") (pinfunction "PC4(ADC4/SDA)_27") (pintype "bidirectional"))
      (node (ref "U4") (pin "27") (pinfunction "PC4(ADC4/SDA)_27") (pintype "bidirectional"))
      (node (ref "U6") (pin "27") (pinfunction "PC4(ADC4/SDA)_27") (pintype "bidirectional"))
    )
    (net (code "113") (name "START_R") (class "Default")
      (node (ref "IC1") (pin "1") (pinfunction "I0_1") (pintype "input"))
      (node (ref "T1") (pin "21/A7") (pinfunction "21/A7/PWM_21/A7") (pintype "bidirectional"))
    )
    (net (code "114") (name "START_R_OUT") (class "Default")
      (node (ref "ETH1") (pin "P$1") (pinfunction "1_P$1") (pintype "bidirectional"))
      (node (ref "IC1") (pin "3") (pinfunction "O_3") (pintype "output"))
    )
    (net (code "115") (name "SUPPLY_V") (class "Default")
      (node (ref "M1") (pin "IN1") (pinfunction "IN1_IN1") (pintype "bidirectional"))
      (node (ref "T1") (pin "6") (pinfunction "6/PWM_6") (pintype "bidirectional"))
    )
    (net (code "116") (name "SUPPLY_V_G") (class "Default")
      (node (ref "ETH6") (pin "P$2") (pinfunction "2_P$2") (pintype "bidirectional"))
      (node (ref "M1") (pin "OUT1") (pinfunction "OUT1_OUT1") (pintype "bidirectional"))
      (node (ref "R17") (pin "2") (pinfunction "2_2") (pintype "passive"))
    )
    (net (code "117") (name "THIS_IS_NOT_CONNECTED_1") (class "Default")
      (node (ref "ISP1") (pin "2") (pinfunction "VCC_2") (pintype "power_in"))
    )
    (net (code "118") (name "THIS_IS_NOT_CONNECTED_2") (class "Default")
      (node (ref "ISP2") (pin "2") (pinfunction "VCC_2") (pintype "power_in"))
    )
    (net (code "119") (name "THIS_IS_NOT_CONNECTED_3") (class "Default")
      (node (ref "ISP3") (pin "2") (pinfunction "VCC_2") (pintype "power_in"))
    )
    (net (code "120") (name "TX1") (class "Default")
      (node (ref "CAN1") (pin "RXI") (pinfunction "RXI_RXI") (pintype "bidirectional"))
      (node (ref "T1") (pin "1") (pinfunction "1/TX1/T_1") (pintype "bidirectional"))
    )
    (net (code "121") (name "TX3") (class "Default")
      (node (ref "O1") (pin "P$2") (pinfunction "RXI_P$2") (pintype "bidirectional"))
      (node (ref "T1") (pin "8") (pinfunction "8/TX3_8") (pintype "bidirectional"))
    )
    (net (code "122") (name "VBAT") (class "Default")
      (node (ref "T1") (pin "VBAT") (pinfunction "VBAT_VBAT") (pintype "power_in"))
    )
    (net (code "123") (name "VDD") (class "Default")
      (node (ref "SJ2") (pin "2") (pinfunction "2_2") (pintype "passive"))
    )
    (net (code "124") (name "VSS") (class "Default")
      (node (ref "SJ1") (pin "2") (pinfunction "2_2") (pintype "passive"))
    )
    (net (code "125") (name "VUSB") (class "Default")
      (node (ref "T1") (pin "VUSB") (pinfunction "VUSB_VUSB") (pintype "power_in"))
    )
    (net (code "126") (name "unconnected-(CAN1-PadCTS)") (class "Default")
      (node (ref "CAN1") (pin "CTS") (pinfunction "CTS_CTS") (pintype "bidirectional"))
    )
    (net (code "127") (name "unconnected-(CAN1-PadDTR)") (class "Default")
      (node (ref "CAN1") (pin "DTR") (pinfunction "DTR_DTR") (pintype "bidirectional"))
    )
    (net (code "128") (name "unconnected-(CAN1-PadSCL)") (class "Default")
      (node (ref "CAN1") (pin "SCL") (pinfunction "SCL_SCL") (pintype "bidirectional"))
    )
    (net (code "129") (name "unconnected-(CAN1-PadSDA)") (class "Default")
      (node (ref "CAN1") (pin "SDA") (pinfunction "SDA_SDA") (pintype "bidirectional"))
    )
    (net (code "130") (name "unconnected-(CAN1-PadVIN)") (class "Default")
      (node (ref "CAN1") (pin "VIN") (pinfunction "VIN_VIN") (pintype "bidirectional"))
    )
    (net (code "131") (name "unconnected-(ETH1-LED1N-PadP$9)") (class "Default")
      (node (ref "ETH1") (pin "P$9") (pinfunction "LED1N_P$9") (pintype "bidirectional"))
    )
    (net (code "132") (name "unconnected-(ETH1-LED1P-PadP$10)") (class "Default")
      (node (ref "ETH1") (pin "P$10") (pinfunction "LED1P_P$10") (pintype "bidirectional"))
    )
    (net (code "133") (name "unconnected-(ETH1-LED2N-PadP$11)") (class "Default")
      (node (ref "ETH1") (pin "P$11") (pinfunction "LED2N_P$11") (pintype "bidirectional"))
    )
    (net (code "134") (name "unconnected-(ETH1-LED2P-PadP$12)") (class "Default")
      (node (ref "ETH1") (pin "P$12") (pinfunction "LED2P_P$12") (pintype "bidirectional"))
    )
    (net (code "135") (name "unconnected-(ETH2-LED1N-PadP$9)") (class "Default")
      (node (ref "ETH2") (pin "P$9") (pinfunction "LED1N_P$9") (pintype "bidirectional"))
    )
    (net (code "136") (name "unconnected-(ETH2-LED1P-PadP$10)") (class "Default")
      (node (ref "ETH2") (pin "P$10") (pinfunction "LED1P_P$10") (pintype "bidirectional"))
    )
    (net (code "137") (name "unconnected-(ETH2-LED2N-PadP$11)") (class "Default")
      (node (ref "ETH2") (pin "P$11") (pinfunction "LED2N_P$11") (pintype "bidirectional"))
    )
    (net (code "138") (name "unconnected-(ETH2-LED2P-PadP$12)") (class "Default")
      (node (ref "ETH2") (pin "P$12") (pinfunction "LED2P_P$12") (pintype "bidirectional"))
    )
    (net (code "139") (name "unconnected-(ETH3-LED1N-PadP$9)") (class "Default")
      (node (ref "ETH3") (pin "P$9") (pinfunction "LED1N_P$9") (pintype "bidirectional"))
    )
    (net (code "140") (name "unconnected-(ETH3-LED1P-PadP$10)") (class "Default")
      (node (ref "ETH3") (pin "P$10") (pinfunction "LED1P_P$10") (pintype "bidirectional"))
    )
    (net (code "141") (name "unconnected-(ETH3-LED2N-PadP$11)") (class "Default")
      (node (ref "ETH3") (pin "P$11") (pinfunction "LED2N_P$11") (pintype "bidirectional"))
    )
    (net (code "142") (name "unconnected-(ETH3-LED2P-PadP$12)") (class "Default")
      (node (ref "ETH3") (pin "P$12") (pinfunction "LED2P_P$12") (pintype "bidirectional"))
    )
    (net (code "143") (name "unconnected-(ETH4-3-PadP$3)") (class "Default")
      (node (ref "ETH4") (pin "P$3") (pinfunction "3_P$3") (pintype "bidirectional"))
    )
    (net (code "144") (name "unconnected-(ETH4-4-PadP$4)") (class "Default")
      (node (ref "ETH4") (pin "P$4") (pinfunction "4_P$4") (pintype "bidirectional"))
    )
    (net (code "145") (name "unconnected-(ETH4-5-PadP$5)") (class "Default")
      (node (ref "ETH4") (pin "P$5") (pinfunction "5_P$5") (pintype "bidirectional"))
    )
    (net (code "146") (name "unconnected-(ETH4-LED1N-PadP$9)") (class "Default")
      (node (ref "ETH4") (pin "P$9") (pinfunction "LED1N_P$9") (pintype "bidirectional"))
    )
    (net (code "147") (name "unconnected-(ETH4-LED1P-PadP$10)") (class "Default")
      (node (ref "ETH4") (pin "P$10") (pinfunction "LED1P_P$10") (pintype "bidirectional"))
    )
    (net (code "148") (name "unconnected-(ETH4-LED2N-PadP$11)") (class "Default")
      (node (ref "ETH4") (pin "P$11") (pinfunction "LED2N_P$11") (pintype "bidirectional"))
    )
    (net (code "149") (name "unconnected-(ETH4-LED2P-PadP$12)") (class "Default")
      (node (ref "ETH4") (pin "P$12") (pinfunction "LED2P_P$12") (pintype "bidirectional"))
    )
    (net (code "150") (name "unconnected-(ETH5-4-PadP$4)") (class "Default")
      (node (ref "ETH5") (pin "P$4") (pinfunction "4_P$4") (pintype "bidirectional"))
    )
    (net (code "151") (name "unconnected-(ETH5-5-PadP$5)") (class "Default")
      (node (ref "ETH5") (pin "P$5") (pinfunction "5_P$5") (pintype "bidirectional"))
    )
    (net (code "152") (name "unconnected-(ETH5-6-PadP$6)") (class "Default")
      (node (ref "ETH5") (pin "P$6") (pinfunction "6_P$6") (pintype "bidirectional"))
    )
    (net (code "153") (name "unconnected-(ETH5-7-PadP$7)") (class "Default")
      (node (ref "ETH5") (pin "P$7") (pinfunction "7_P$7") (pintype "bidirectional"))
    )
    (net (code "154") (name "unconnected-(ETH5-8-PadP$8)") (class "Default")
      (node (ref "ETH5") (pin "P$8") (pinfunction "8_P$8") (pintype "bidirectional"))
    )
    (net (code "155") (name "unconnected-(ETH5-LED1N-PadP$9)") (class "Default")
      (node (ref "ETH5") (pin "P$9") (pinfunction "LED1N_P$9") (pintype "bidirectional"))
    )
    (net (code "156") (name "unconnected-(ETH5-LED1P-PadP$10)") (class "Default")
      (node (ref "ETH5") (pin "P$10") (pinfunction "LED1P_P$10") (pintype "bidirectional"))
    )
    (net (code "157") (name "unconnected-(ETH5-LED2N-PadP$11)") (class "Default")
      (node (ref "ETH5") (pin "P$11") (pinfunction "LED2N_P$11") (pintype "bidirectional"))
    )
    (net (code "158") (name "unconnected-(ETH5-LED2P-PadP$12)") (class "Default")
      (node (ref "ETH5") (pin "P$12") (pinfunction "LED2P_P$12") (pintype "bidirectional"))
    )
    (net (code "159") (name "unconnected-(ETH6-7-PadP$7)") (class "Default")
      (node (ref "ETH6") (pin "P$7") (pinfunction "7_P$7") (pintype "bidirectional"))
    )
    (net (code "160") (name "unconnected-(ETH6-8-PadP$8)") (class "Default")
      (node (ref "ETH6") (pin "P$8") (pinfunction "8_P$8") (pintype "bidirectional"))
    )
    (net (code "161") (name "unconnected-(ETH6-LED1N-PadP$9)") (class "Default")
      (node (ref "ETH6") (pin "P$9") (pinfunction "LED1N_P$9") (pintype "bidirectional"))
    )
    (net (code "162") (name "unconnected-(ETH6-LED1P-PadP$10)") (class "Default")
      (node (ref "ETH6") (pin "P$10") (pinfunction "LED1P_P$10") (pintype "bidirectional"))
    )
    (net (code "163") (name "unconnected-(ETH6-LED2N-PadP$11)") (class "Default")
      (node (ref "ETH6") (pin "P$11") (pinfunction "LED2N_P$11") (pintype "bidirectional"))
    )
    (net (code "164") (name "unconnected-(ETH6-LED2P-PadP$12)") (class "Default")
      (node (ref "ETH6") (pin "P$12") (pinfunction "LED2P_P$12") (pintype "bidirectional"))
    )
    (net (code "165") (name "unconnected-(ETH7-3-PadP$3)") (class "Default")
      (node (ref "ETH7") (pin "P$3") (pinfunction "3_P$3") (pintype "bidirectional"))
    )
    (net (code "166") (name "unconnected-(ETH7-4-PadP$4)") (class "Default")
      (node (ref "ETH7") (pin "P$4") (pinfunction "4_P$4") (pintype "bidirectional"))
    )
    (net (code "167") (name "unconnected-(ETH7-7-PadP$7)") (class "Default")
      (node (ref "ETH7") (pin "P$7") (pinfunction "7_P$7") (pintype "bidirectional"))
    )
    (net (code "168") (name "unconnected-(ETH7-LED1N-PadP$9)") (class "Default")
      (node (ref "ETH7") (pin "P$9") (pinfunction "LED1N_P$9") (pintype "bidirectional"))
    )
    (net (code "169") (name "unconnected-(ETH7-LED1P-PadP$10)") (class "Default")
      (node (ref "ETH7") (pin "P$10") (pinfunction "LED1P_P$10") (pintype "bidirectional"))
    )
    (net (code "170") (name "unconnected-(ETH7-LED2N-PadP$11)") (class "Default")
      (node (ref "ETH7") (pin "P$11") (pinfunction "LED2N_P$11") (pintype "bidirectional"))
    )
    (net (code "171") (name "unconnected-(ETH7-LED2P-PadP$12)") (class "Default")
      (node (ref "ETH7") (pin "P$12") (pinfunction "LED2P_P$12") (pintype "bidirectional"))
    )
    (net (code "172") (name "unconnected-(O1-DTR-PadP$1)") (class "Default")
      (node (ref "O1") (pin "P$1") (pinfunction "DTR_P$1") (pintype "bidirectional"))
    )
    (net (code "173") (name "unconnected-(RTC1-32KHZ-PadP$6)") (class "Default")
      (node (ref "RTC1") (pin "P$6") (pinfunction "32KHZ_P$6") (pintype "bidirectional"))
    )
    (net (code "174") (name "unconnected-(RTC1-BAT-PadP$5)") (class "Default")
      (node (ref "RTC1") (pin "P$5") (pinfunction "BAT_P$5") (pintype "bidirectional"))
    )
    (net (code "175") (name "unconnected-(RTC1-RST-PadP$8)") (class "Default")
      (node (ref "RTC1") (pin "P$8") (pinfunction "RST_P$8") (pintype "bidirectional"))
    )
    (net (code "176") (name "unconnected-(RTC1-SQW-PadP$7)") (class "Default")
      (node (ref "RTC1") (pin "P$7") (pinfunction "SQW_P$7") (pintype "bidirectional"))
    )
    (net (code "177") (name "unconnected-(SHT1-ADDR-PadADR)") (class "Default")
      (node (ref "SHT1") (pin "ADR") (pinfunction "ADDR_ADR") (pintype "bidirectional"))
    )
    (net (code "178") (name "unconnected-(SHT1-ALERT-PadALR)") (class "Default")
      (node (ref "SHT1") (pin "ALR") (pinfunction "ALERT_ALR") (pintype "bidirectional"))
    )
    (net (code "179") (name "unconnected-(SHT1-PadRST)") (class "Default")
      (node (ref "SHT1") (pin "RST") (pinfunction "RST_RST") (pintype "bidirectional"))
    )
    (net (code "180") (name "unconnected-(T1-13{slash}SCK{slash}LED-Pad13)") (class "Default")
      (node (ref "T1") (pin "13") (pinfunction "13/SCK/LED_13") (pintype "bidirectional"))
    )
    (net (code "181") (name "unconnected-(T1-23{slash}A9{slash}T{slash}PWM-Pad23{slash}A9)") (class "Default")
      (node (ref "T1") (pin "23/A9") (pinfunction "23/A9/T/PWM_23/A9") (pintype "bidirectional"))
    )
    (net (code "182") (name "unconnected-(T1-A14{slash}DAC-PadRESET{slash}DAC)") (class "Default")
      (node (ref "T1") (pin "RESET/DAC") (pinfunction "A14/DAC_RESET/DAC") (pintype "bidirectional"))
    )
    (net (code "183") (name "unconnected-(T1-PadA10)") (class "Default")
      (node (ref "T1") (pin "A10") (pinfunction "A10_A10") (pintype "bidirectional"))
    )
    (net (code "184") (name "unconnected-(T1-PadPGM)") (class "Default")
      (node (ref "T1") (pin "PGM") (pinfunction "PGM_PGM") (pintype "bidirectional"))
    )
    (net (code "185") (name "unconnected-(U3-ADC6-Pad19)") (class "Default")
      (node (ref "U3") (pin "19") (pinfunction "ADC6_19") (pintype "bidirectional"))
    )
    (net (code "186") (name "unconnected-(U3-ADC7-Pad22)") (class "Default")
      (node (ref "U3") (pin "22") (pinfunction "ADC7_22") (pintype "bidirectional"))
    )
    (net (code "187") (name "unconnected-(U3-PB0(ICP)-Pad12)") (class "Default")
      (node (ref "U3") (pin "12") (pinfunction "PB0(ICP)_12") (pintype "bidirectional"))
    )
    (net (code "188") (name "unconnected-(U3-PB1(OC1A)-Pad13)") (class "Default")
      (node (ref "U3") (pin "13") (pinfunction "PB1(OC1A)_13") (pintype "bidirectional"))
    )
    (net (code "189") (name "unconnected-(U3-PB2(SS{slash}OC1B)-Pad14)") (class "Default")
      (node (ref "U3") (pin "14") (pinfunction "PB2(SS/OC1B)_14") (pintype "bidirectional"))
    )
    (net (code "190") (name "unconnected-(U3-PC0(ADC0)-Pad23)") (class "Default")
      (node (ref "U3") (pin "23") (pinfunction "PC0(ADC0)_23") (pintype "bidirectional"))
    )
    (net (code "191") (name "unconnected-(U3-PC1(ADC1)-Pad24)") (class "Default")
      (node (ref "U3") (pin "24") (pinfunction "PC1(ADC1)_24") (pintype "bidirectional"))
    )
    (net (code "192") (name "unconnected-(U3-PC2(ADC2)-Pad25)") (class "Default")
      (node (ref "U3") (pin "25") (pinfunction "PC2(ADC2)_25") (pintype "bidirectional"))
    )
    (net (code "193") (name "unconnected-(U3-PC3(ADC3)-Pad26)") (class "Default")
      (node (ref "U3") (pin "26") (pinfunction "PC3(ADC3)_26") (pintype "bidirectional"))
    )
    (net (code "194") (name "unconnected-(U3-PD2(INT0)-Pad32)") (class "Default")
      (node (ref "U3") (pin "32") (pinfunction "PD2(INT0)_32") (pintype "bidirectional"))
    )
    (net (code "195") (name "unconnected-(U3-PD4(XCK{slash}T0)-Pad2)") (class "Default")
      (node (ref "U3") (pin "2") (pinfunction "PD4(XCK/T0)_2") (pintype "bidirectional"))
    )
    (net (code "196") (name "unconnected-(U3-PD5(T1)-Pad9)") (class "Default")
      (node (ref "U3") (pin "9") (pinfunction "PD5(T1)_9") (pintype "bidirectional"))
    )
    (net (code "197") (name "unconnected-(U3-PD6(AIN0)-Pad10)") (class "Default")
      (node (ref "U3") (pin "10") (pinfunction "PD6(AIN0)_10") (pintype "bidirectional"))
    )
    (net (code "198") (name "unconnected-(U3-PD7(AIN1)-Pad11)") (class "Default")
      (node (ref "U3") (pin "11") (pinfunction "PD7(AIN1)_11") (pintype "bidirectional"))
    )
    (net (code "199") (name "unconnected-(U4-ADC6-Pad19)") (class "Default")
      (node (ref "U4") (pin "19") (pinfunction "ADC6_19") (pintype "bidirectional"))
    )
    (net (code "200") (name "unconnected-(U4-ADC7-Pad22)") (class "Default")
      (node (ref "U4") (pin "22") (pinfunction "ADC7_22") (pintype "bidirectional"))
    )
    (net (code "201") (name "unconnected-(U4-PB0(ICP)-Pad12)") (class "Default")
      (node (ref "U4") (pin "12") (pinfunction "PB0(ICP)_12") (pintype "bidirectional"))
    )
    (net (code "202") (name "unconnected-(U4-PB1(OC1A)-Pad13)") (class "Default")
      (node (ref "U4") (pin "13") (pinfunction "PB1(OC1A)_13") (pintype "bidirectional"))
    )
    (net (code "203") (name "unconnected-(U4-PB2(SS{slash}OC1B)-Pad14)") (class "Default")
      (node (ref "U4") (pin "14") (pinfunction "PB2(SS/OC1B)_14") (pintype "bidirectional"))
    )
    (net (code "204") (name "unconnected-(U4-PC0(ADC0)-Pad23)") (class "Default")
      (node (ref "U4") (pin "23") (pinfunction "PC0(ADC0)_23") (pintype "bidirectional"))
    )
    (net (code "205") (name "unconnected-(U4-PC1(ADC1)-Pad24)") (class "Default")
      (node (ref "U4") (pin "24") (pinfunction "PC1(ADC1)_24") (pintype "bidirectional"))
    )
    (net (code "206") (name "unconnected-(U4-PC2(ADC2)-Pad25)") (class "Default")
      (node (ref "U4") (pin "25") (pinfunction "PC2(ADC2)_25") (pintype "bidirectional"))
    )
    (net (code "207") (name "unconnected-(U4-PC3(ADC3)-Pad26)") (class "Default")
      (node (ref "U4") (pin "26") (pinfunction "PC3(ADC3)_26") (pintype "bidirectional"))
    )
    (net (code "208") (name "unconnected-(U4-PD2(INT0)-Pad32)") (class "Default")
      (node (ref "U4") (pin "32") (pinfunction "PD2(INT0)_32") (pintype "bidirectional"))
    )
    (net (code "209") (name "unconnected-(U4-PD4(XCK{slash}T0)-Pad2)") (class "Default")
      (node (ref "U4") (pin "2") (pinfunction "PD4(XCK/T0)_2") (pintype "bidirectional"))
    )
    (net (code "210") (name "unconnected-(U4-PD5(T1)-Pad9)") (class "Default")
      (node (ref "U4") (pin "9") (pinfunction "PD5(T1)_9") (pintype "bidirectional"))
    )
    (net (code "211") (name "unconnected-(U4-PD6(AIN0)-Pad10)") (class "Default")
      (node (ref "U4") (pin "10") (pinfunction "PD6(AIN0)_10") (pintype "bidirectional"))
    )
    (net (code "212") (name "unconnected-(U4-PD7(AIN1)-Pad11)") (class "Default")
      (node (ref "U4") (pin "11") (pinfunction "PD7(AIN1)_11") (pintype "bidirectional"))
    )
    (net (code "213") (name "unconnected-(U6-PB0(ICP)-Pad12)") (class "Default")
      (node (ref "U6") (pin "12") (pinfunction "PB0(ICP)_12") (pintype "bidirectional"))
    )
    (net (code "214") (name "unconnected-(U6-PB1(OC1A)-Pad13)") (class "Default")
      (node (ref "U6") (pin "13") (pinfunction "PB1(OC1A)_13") (pintype "bidirectional"))
    )
    (net (code "215") (name "unconnected-(U6-PB2(SS{slash}OC1B)-Pad14)") (class "Default")
      (node (ref "U6") (pin "14") (pinfunction "PB2(SS/OC1B)_14") (pintype "bidirectional"))
    )
    (net (code "216") (name "unconnected-(U6-PB6(XTAL1{slash}TOSC1)-Pad7)") (class "Default")
      (node (ref "U6") (pin "7") (pinfunction "PB6(XTAL1/TOSC1)_7") (pintype "bidirectional"))
    )
    (net (code "217") (name "unconnected-(U6-PB7(XTAL2{slash}TOSC2)-Pad8)") (class "Default")
      (node (ref "U6") (pin "8") (pinfunction "PB7(XTAL2/TOSC2)_8") (pintype "bidirectional"))
    )
    (net (code "218") (name "unconnected-(U6-PD6(AIN0)-Pad10)") (class "Default")
      (node (ref "U6") (pin "10") (pinfunction "PD6(AIN0)_10") (pintype "bidirectional"))
    )
    (net (code "219") (name "unconnected-(U6-PD7(AIN1)-Pad11)") (class "Default")
      (node (ref "U6") (pin "11") (pinfunction "PD7(AIN1)_11") (pintype "bidirectional"))
    )
  )
)
